# SCH_-_RC2014-_Dev_V1_1_-_freeroute.net
KiCad netlist of a schematic drawn in EasyEDA
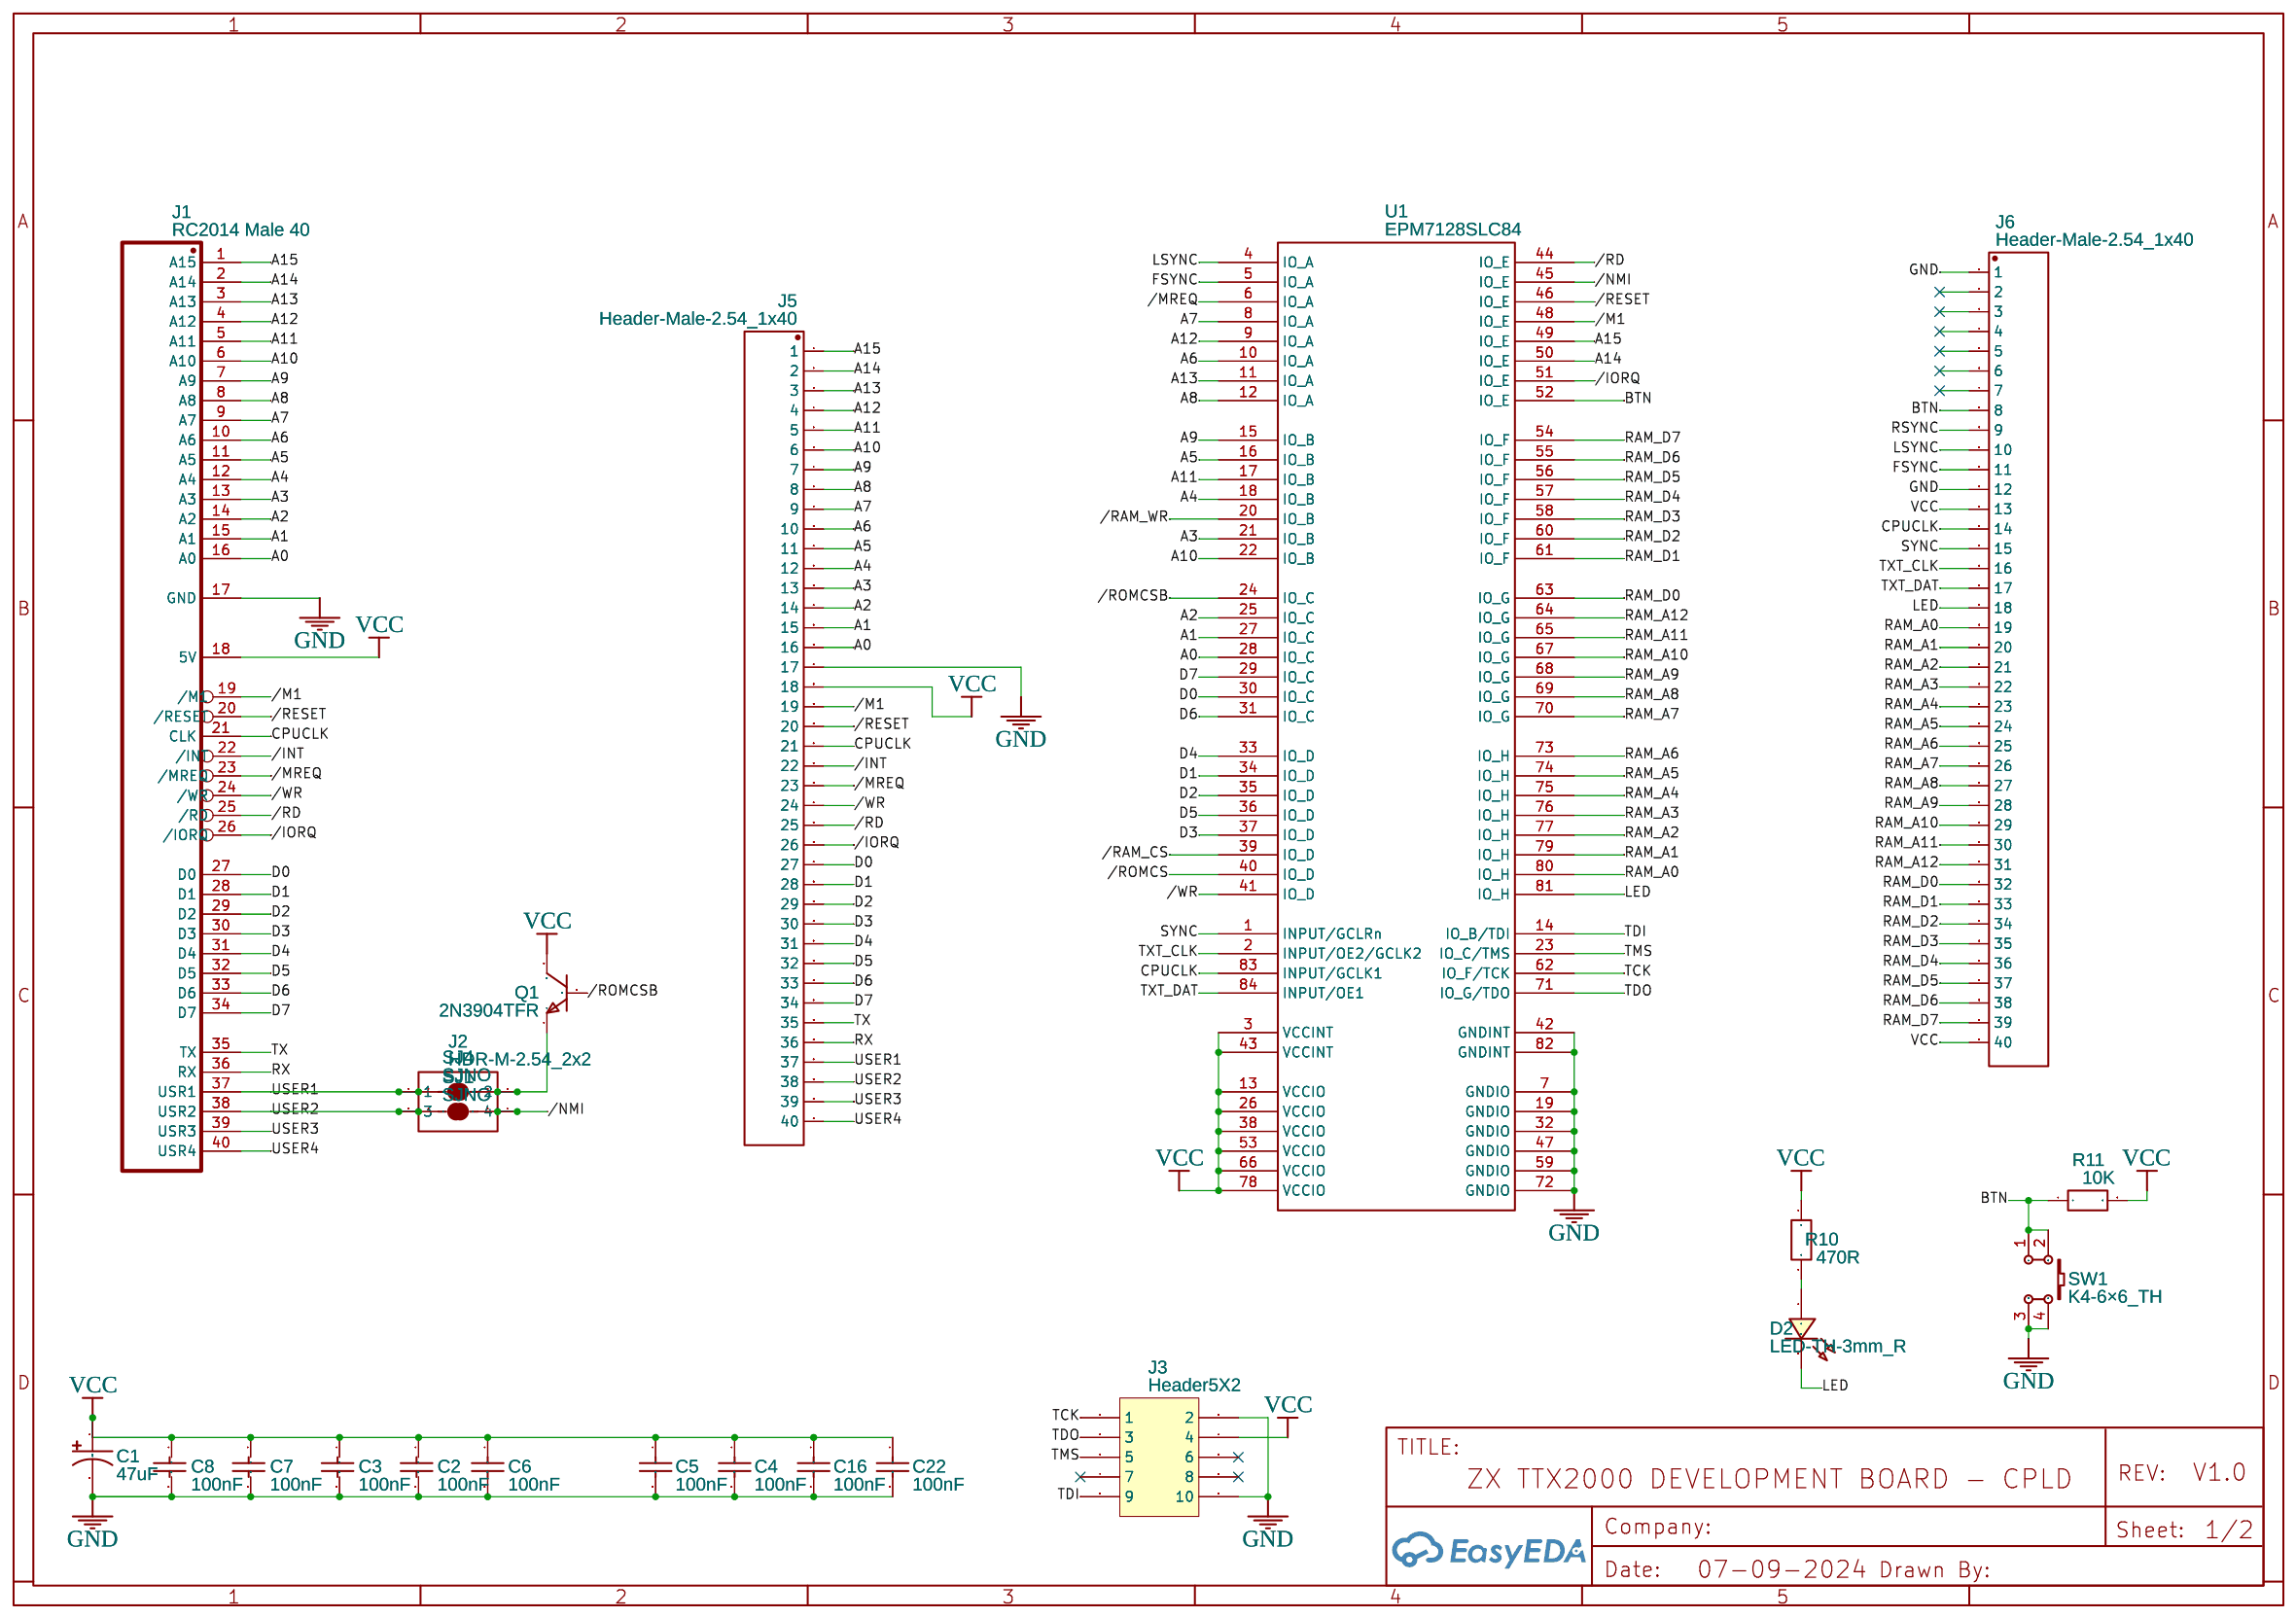
[diagram p0: SCH - RC2014 - Teletext Dev V1.0]
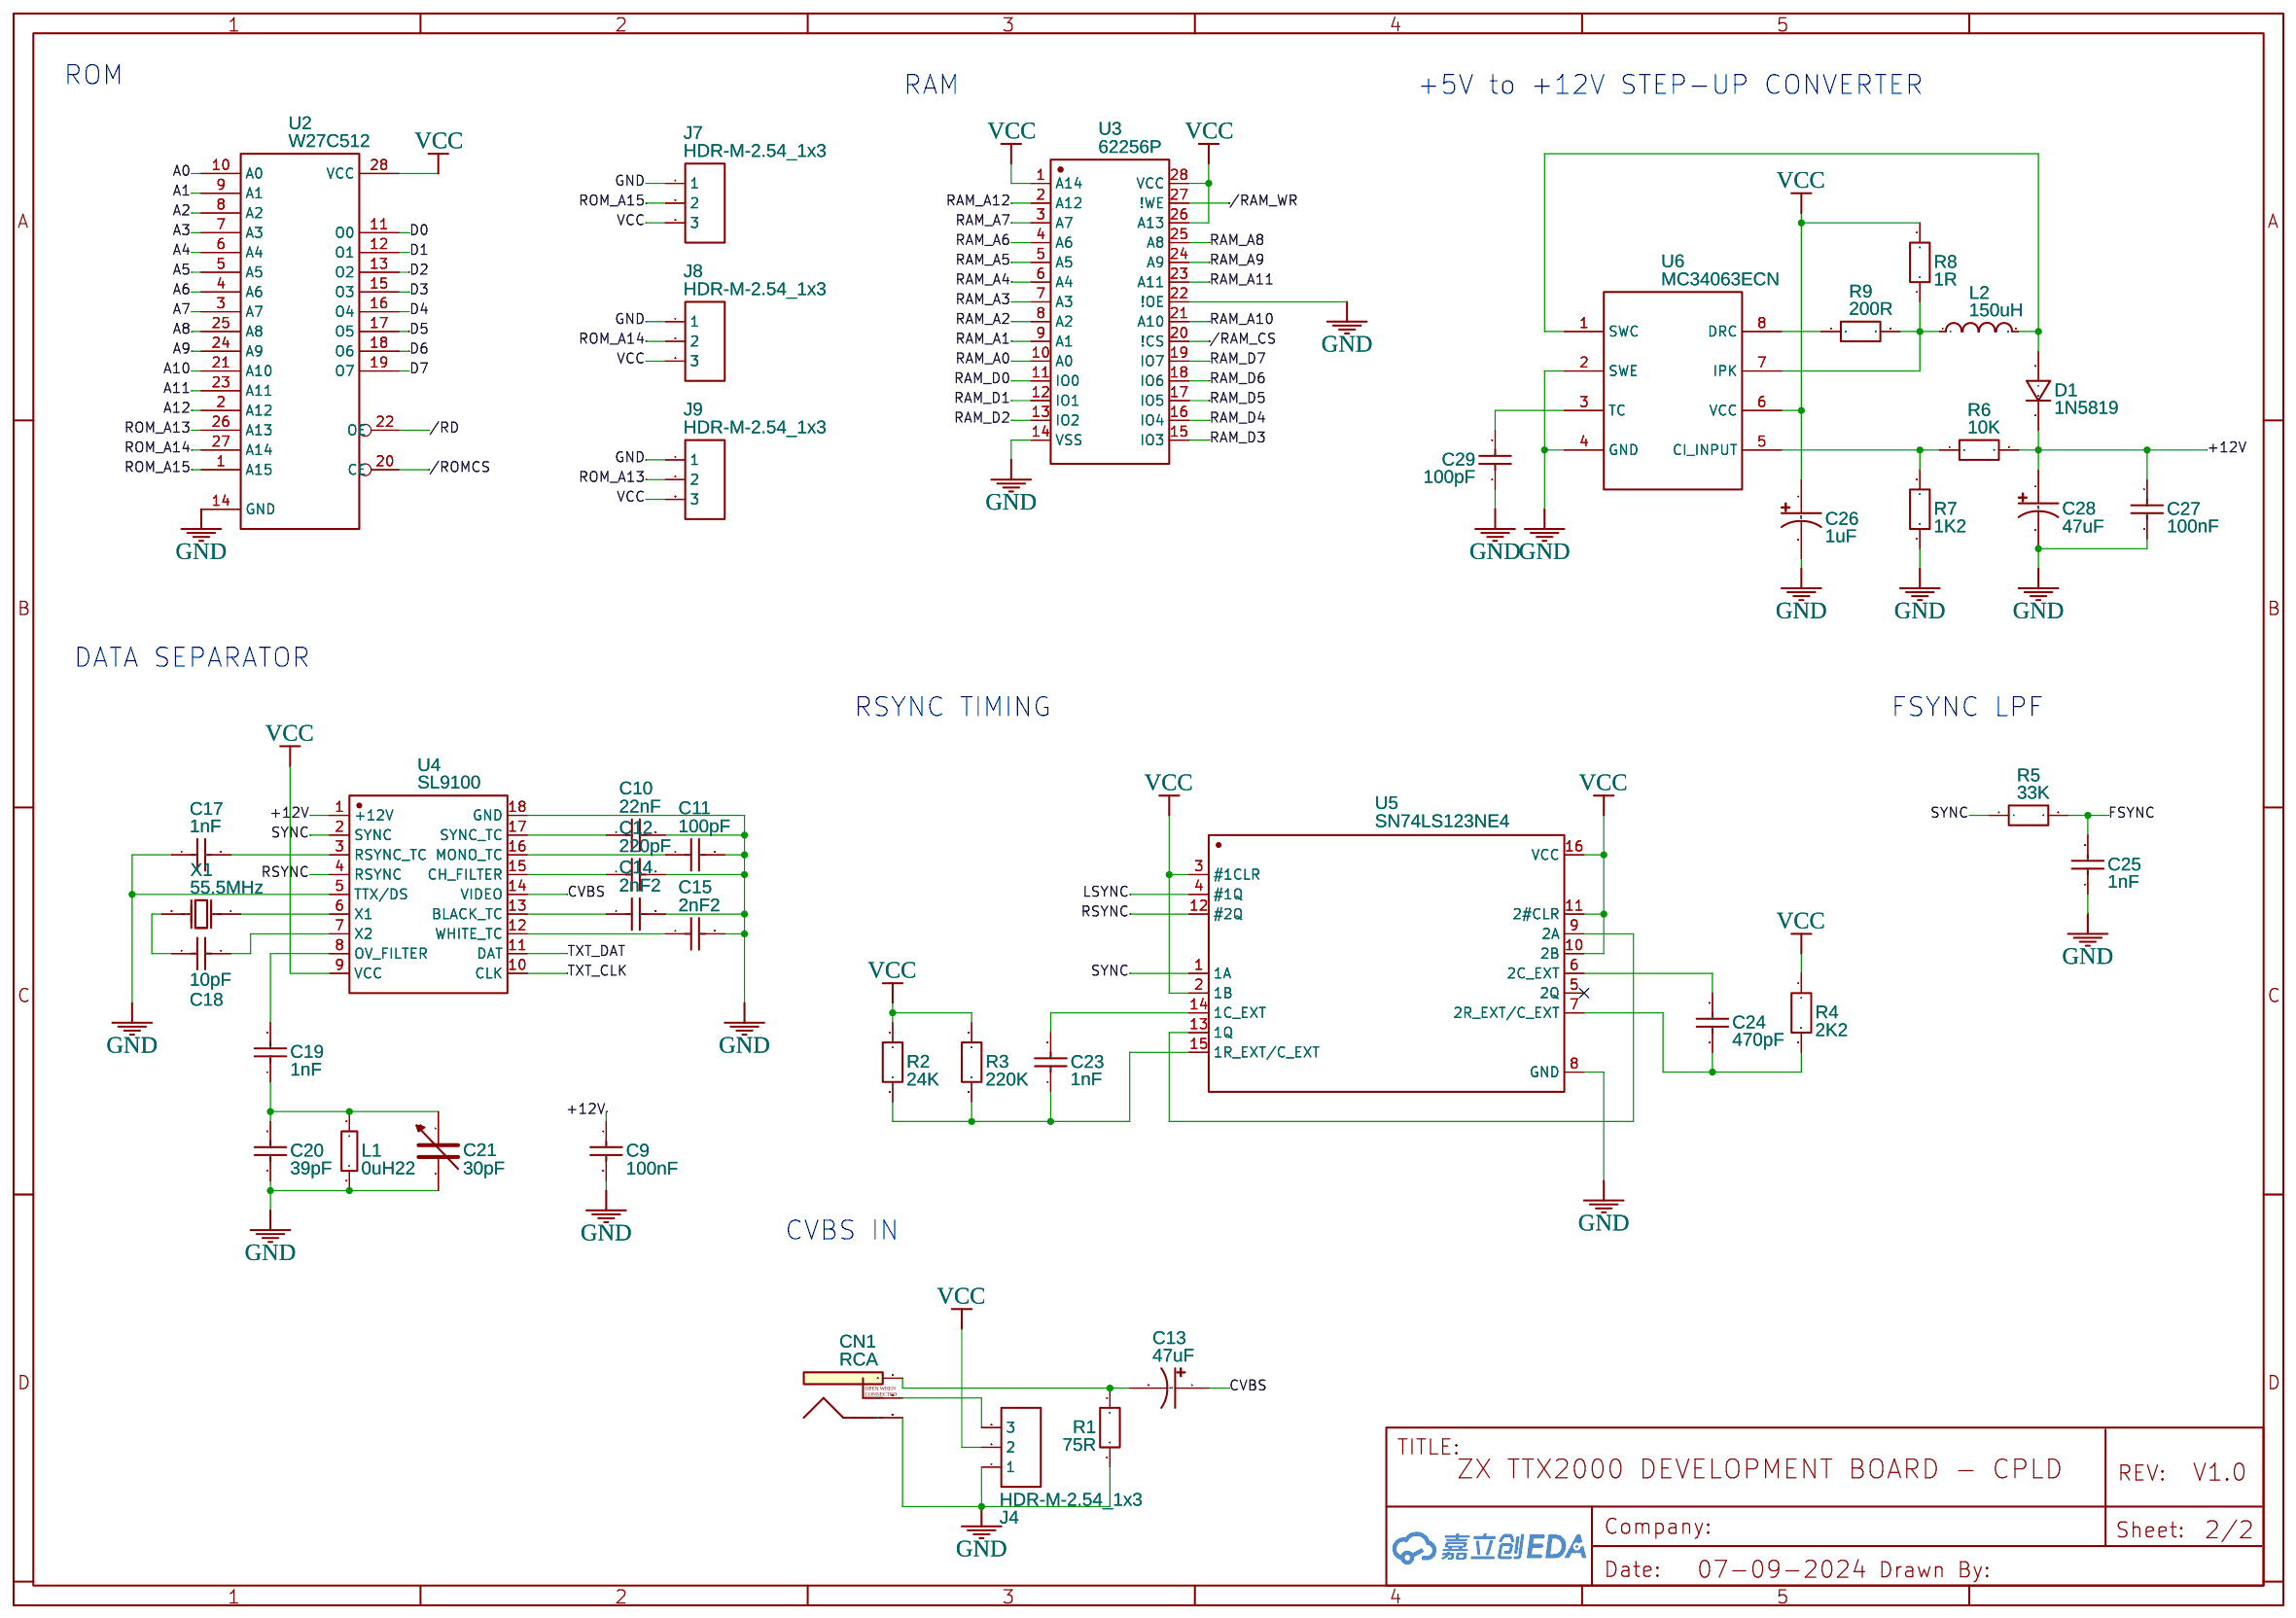
[diagram p1: SCH - ROM & RAM]
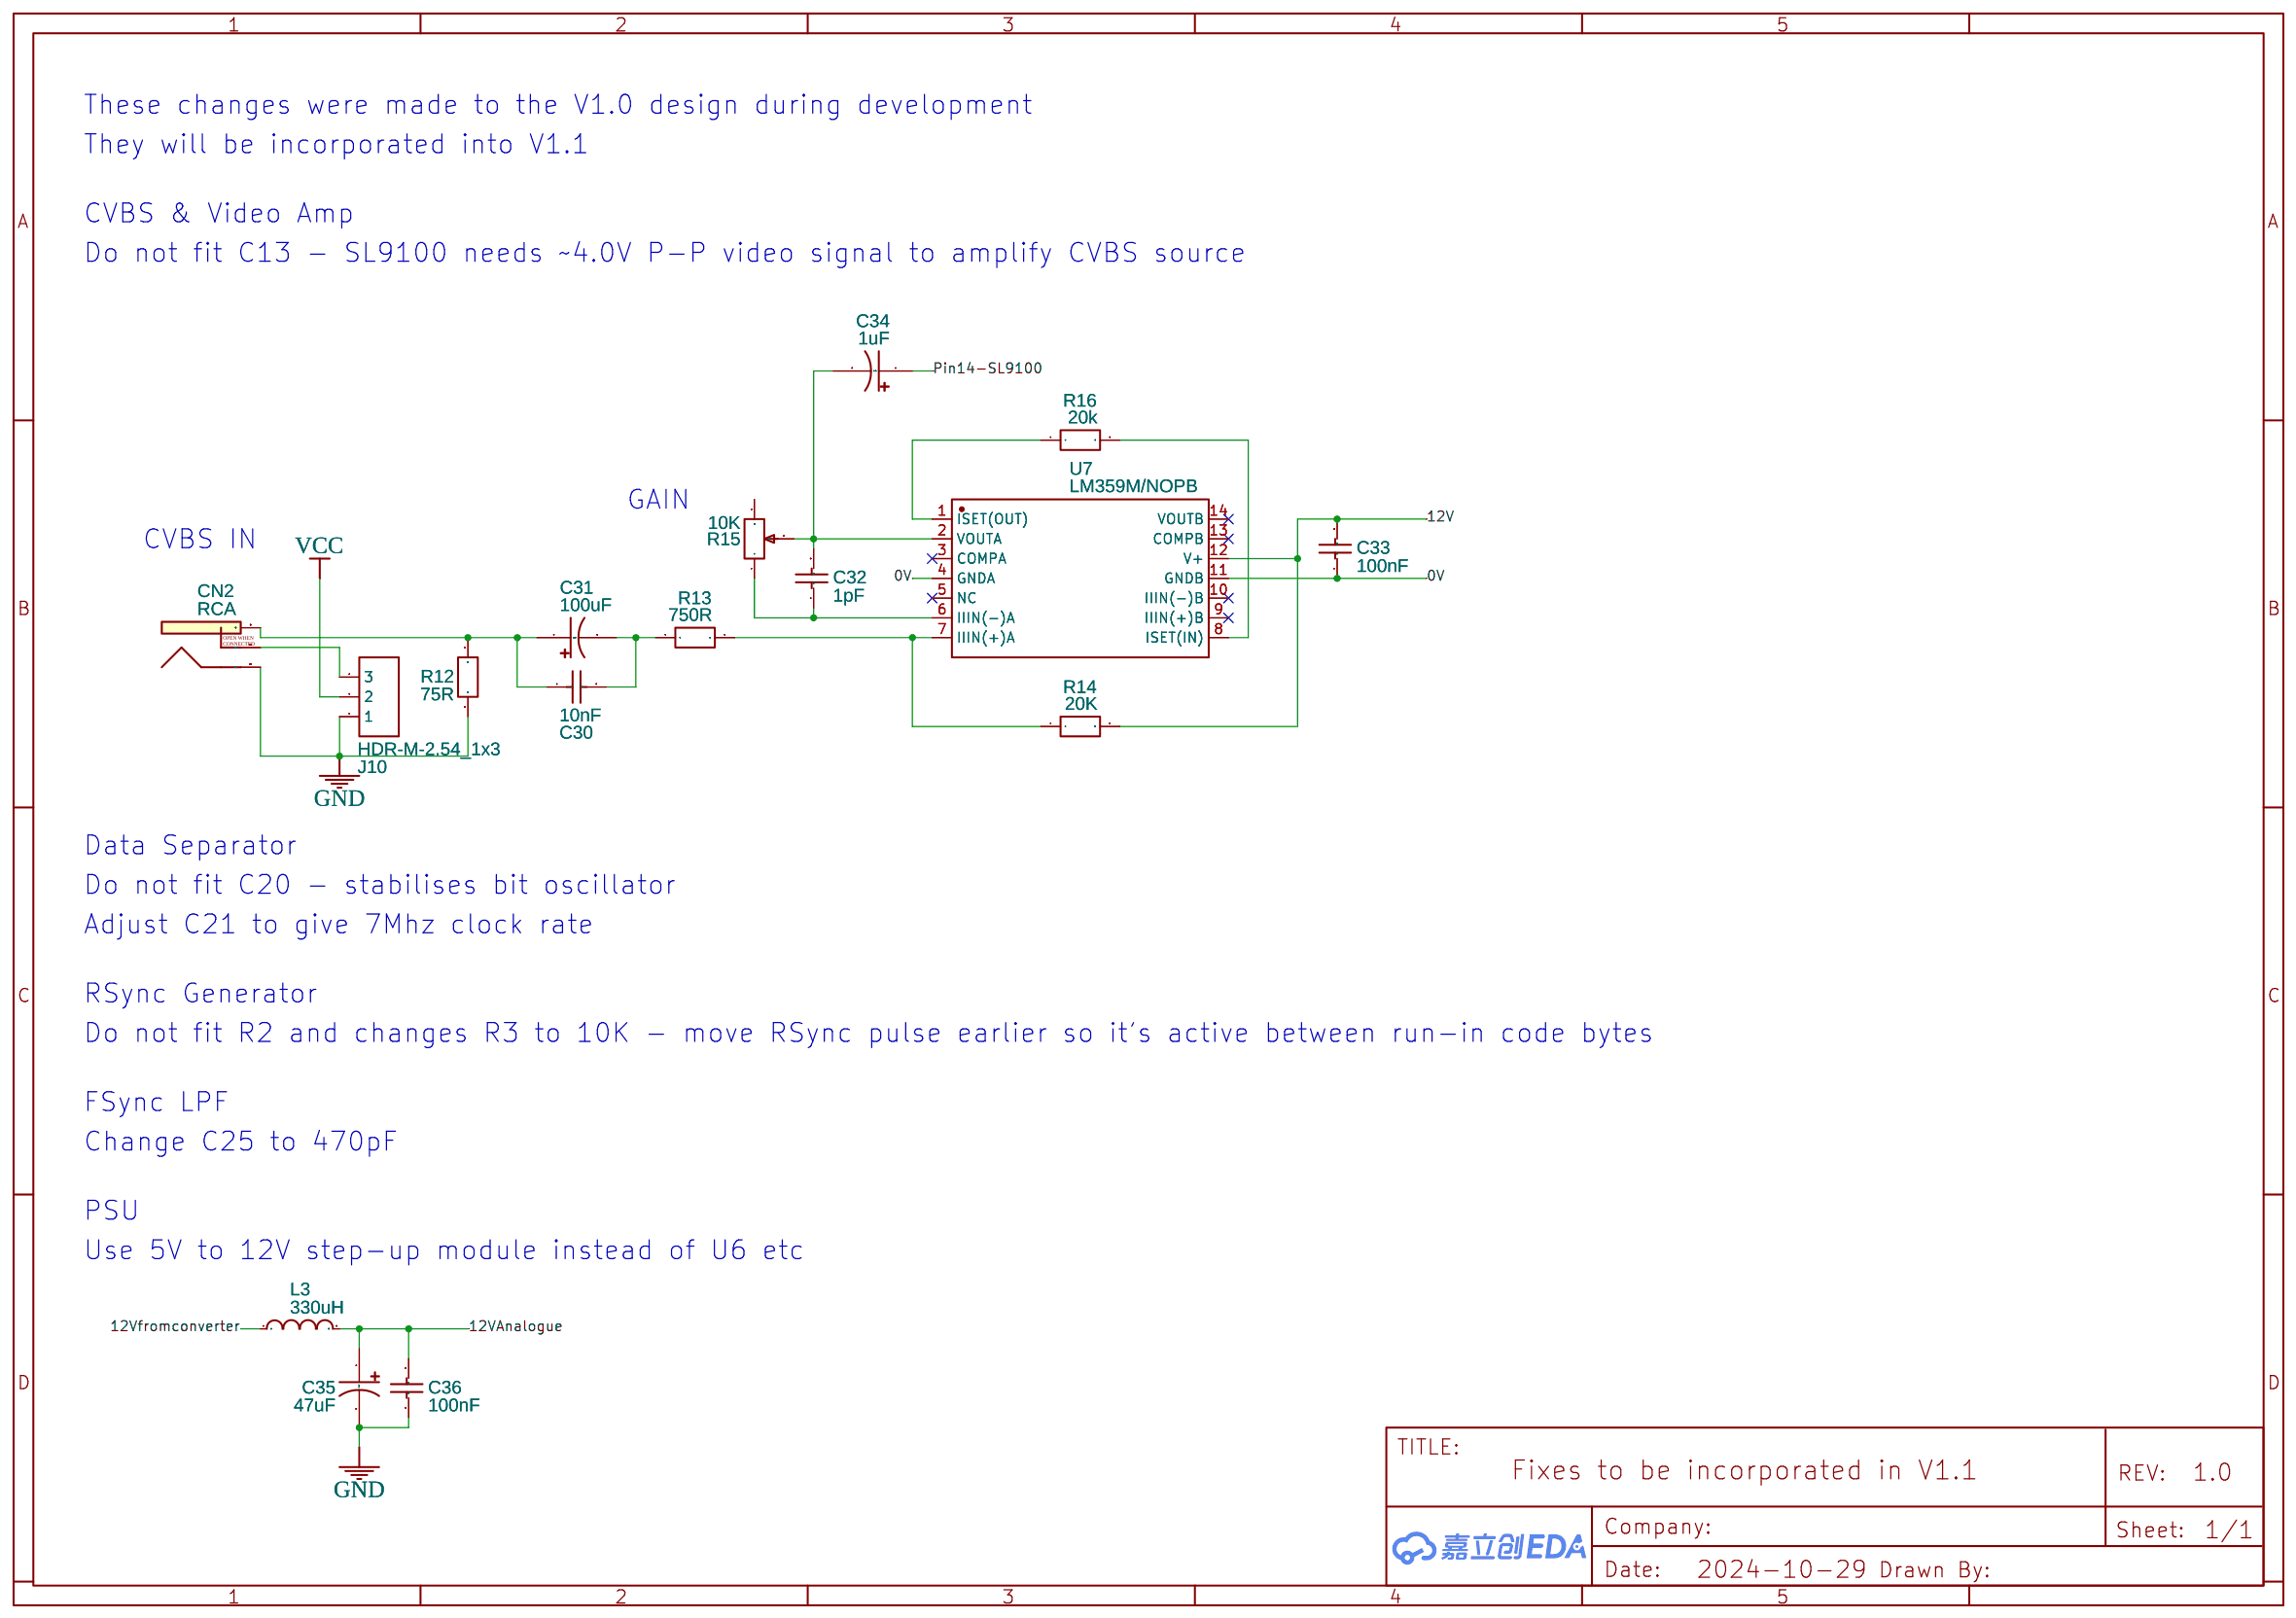
[diagram p2: Fixes]

(export (version "E")
  (design (tool "Eeschema 10.0.6"))
  (components
    (comp (ref "C1")
      (value "47uF")
      (fields
        (field (name "BOM_Manufacturer Part") "KM1H470ME110A00CV0")
        (field (name "BOM_Supplier Part") "C190654")
      )
      (libsource (lib "") (part "KM1H470ME110A00CV0"))
    )
    (comp (ref "C2")
      (value "100nF")
      (fields
        (field (name "BOM_Manufacturer Part") "100nF (104) ±20% 100V")
        (field (name "BOM_Supplier Part") "C72322")
      )
      (libsource (lib "") (part "100nF (104) ±20% 100V_1"))
    )
    (comp (ref "C3")
      (value "100nF")
      (fields
        (field (name "BOM_Manufacturer Part") "100nF (104) ±20% 100V")
        (field (name "BOM_Supplier Part") "C72322")
      )
      (libsource (lib "") (part "100nF (104) ±20% 100V_1"))
    )
    (comp (ref "C4")
      (value "100nF")
      (fields
        (field (name "BOM_Manufacturer Part") "100nF (104) ±20% 100V")
        (field (name "BOM_Supplier Part") "C72322")
      )
      (libsource (lib "") (part "100nF (104) ±20% 100V"))
    )
    (comp (ref "C5")
      (value "100nF")
      (fields
        (field (name "BOM_Manufacturer Part") "100nF (104) ±20% 100V")
        (field (name "BOM_Supplier Part") "C72322")
      )
      (libsource (lib "") (part "100nF (104) ±20% 100V"))
    )
    (comp (ref "C6")
      (value "100nF")
      (fields
        (field (name "BOM_Manufacturer Part") "100nF (104) ±20% 100V")
        (field (name "BOM_Supplier Part") "C72322")
      )
      (libsource (lib "") (part "100nF (104) ±20% 100V"))
    )
    (comp (ref "C7")
      (value "100nF")
      (fields
        (field (name "BOM_Manufacturer Part") "100nF (104) ±20% 100V")
        (field (name "BOM_Supplier Part") "C72322")
      )
      (libsource (lib "") (part "100nF (104) ±20% 100V_1"))
    )
    (comp (ref "C8")
      (value "100nF")
      (fields
        (field (name "BOM_Manufacturer Part") "100nF (104) ±20% 100V")
        (field (name "BOM_Supplier Part") "C72322")
      )
      (libsource (lib "") (part "100nF (104) ±20% 100V_1"))
    )
    (comp (ref "C16")
      (value "100nF")
      (fields
        (field (name "BOM_Manufacturer Part") "100nF (104) ±20% 100V")
        (field (name "BOM_Supplier Part") "C72322")
      )
      (libsource (lib "") (part "100nF (104) ±20% 100V"))
    )
    (comp (ref "C22")
      (value "100nF")
      (fields
        (field (name "BOM_Manufacturer Part") "100nF (104) ±20% 100V")
        (field (name "BOM_Supplier Part") "C72322")
      )
      (libsource (lib "") (part "100nF (104) ±20% 100V"))
    )
    (comp (ref "D2")
      (value "LED-TH-3mm_R")
      (fields
        (field (name "BOM_Manufacturer Part") "204-10SDRD/S530-A3-L")
        (field (name "BOM_Supplier Part") "C84774")
      )
      (libsource (lib "") (part "LED-TH-3mm_R"))
    )
    (comp (ref "J1") (value "RC2014 Male 40") (libsource (lib "") (part "RC2014 Male 40")))
    (comp (ref "J2")
      (value "HDR-M-2.54_2x2")
      (fields (field (name "BOM_Supplier Part") "C66690"))
      (libsource (lib "") (part "HDR-M-2.54_2x2"))
    )
    (comp (ref "J3")
      (value "Header5X2")
      (fields
        (field (name "BOM_Manufacturer Part") "SBH11-PBPC-D05-ST-BK")
        (field (name "BOM_Supplier Part") "S9169-ND")
      )
      (libsource (lib "") (part "Header5X2"))
    )
    (comp (ref "J5")
      (value "Header-Male-2.54_1x40")
      (fields
        (field (name "BOM_Manufacturer Part") "2.54mm 1x40P")
        (field (name "BOM_Supplier Part") "C2337")
      )
      (libsource (lib "") (part "Header-Male-2.54_1x40_1"))
    )
    (comp (ref "J6")
      (value "Header-Male-2.54_1x40")
      (fields
        (field (name "BOM_Manufacturer Part") "2.54mm 1x40P")
        (field (name "BOM_Supplier Part") "C2337")
      )
      (libsource (lib "") (part "Header-Male-2.54_1x40"))
    )
    (comp (ref "Q1")
      (value "2N3904TFR")
      (fields (field (name "BOM_Supplier Part") "C258185"))
      (libsource (lib "") (part "2N3904TFR"))
    )
    (comp (ref "R10") (value "470R") (libsource (lib "") (part "R_AXIAL-0.3_EU_1")))
    (comp (ref "R11") (value "10K") (libsource (lib "") (part "R_AXIAL-0.3_EU")))
    (comp (ref "SJ1") (value "SJNO") (libsource (lib "") (part "SOLDERJUMPERNO")))
    (comp (ref "SJ4") (value "SJNO") (libsource (lib "") (part "SOLDERJUMPERNO")))
    (comp (ref "SW1")
      (value "K4-6×6_TH")
      (fields
        (field (name "BOM_Manufacturer Part") "K2-1102DP-E4SW-04")
        (field (name "BOM_Supplier Part") "C136684")
      )
      (libsource (lib "") (part "K4-6×6_TH"))
    )
    (comp (ref "U1")
      (value "EPM7128SLC84")
      (fields (field (name "BOM_Supplier Part") "692-Z8S18020VEG"))
      (libsource (lib "") (part "EPM7128SLC84"))
    )
    (comp (ref "C9")
      (value "100nF")
      (fields
        (field (name "BOM_Manufacturer Part") "100nF (104) ±20% 100V")
        (field (name "BOM_Supplier Part") "C72322")
      )
      (libsource (lib "") (part "100nF (104) ±20% 100V"))
    )
    (comp (ref "C10")
      (value "22nF")
      (fields
        (field (name "BOM_Manufacturer Part") "100nF (104) ±20% 100V")
        (field (name "BOM_Supplier Part") "C72322")
      )
      (libsource (lib "") (part "100nF (104) ±20% 100V_2"))
    )
    (comp (ref "C11")
      (value "100pF")
      (fields
        (field (name "BOM_Manufacturer Part") "100nF (104) ±20% 100V")
        (field (name "BOM_Supplier Part") "C72322")
      )
      (libsource (lib "") (part "100nF (104) ±20% 100V_2"))
    )
    (comp (ref "C12")
      (value "220pF")
      (fields
        (field (name "BOM_Manufacturer Part") "100nF (104) ±20% 100V")
        (field (name "BOM_Supplier Part") "C72322")
      )
      (libsource (lib "") (part "100nF (104) ±20% 100V_2"))
    )
    (comp (ref "C13")
      (value "47uF")
      (fields
        (field (name "BOM_Manufacturer Part") "KM1H470ME110A00CV0")
        (field (name "BOM_Supplier Part") "C190654")
      )
      (libsource (lib "") (part "KM1H470ME110A00CV0_1"))
    )
    (comp (ref "C14")
      (value "2nF2")
      (fields
        (field (name "BOM_Manufacturer Part") "100nF (104) ±20% 100V")
        (field (name "BOM_Supplier Part") "C72322")
      )
      (libsource (lib "") (part "100nF (104) ±20% 100V_2"))
    )
    (comp (ref "C15")
      (value "2nF2")
      (fields
        (field (name "BOM_Manufacturer Part") "100nF (104) ±20% 100V")
        (field (name "BOM_Supplier Part") "C72322")
      )
      (libsource (lib "") (part "100nF (104) ±20% 100V_2"))
    )
    (comp (ref "C17")
      (value "1nF")
      (fields
        (field (name "BOM_Manufacturer Part") "100nF (104) ±20% 100V")
        (field (name "BOM_Supplier Part") "C72322")
      )
      (libsource (lib "") (part "100nF (104) ±20% 100V_2"))
    )
    (comp (ref "C18")
      (value "10pF")
      (fields
        (field (name "BOM_Manufacturer Part") "100nF (104) ±20% 100V")
        (field (name "BOM_Supplier Part") "C72322")
      )
      (libsource (lib "") (part "100nF (104) ±20% 100V_4"))
    )
    (comp (ref "C19")
      (value "1nF")
      (fields
        (field (name "BOM_Manufacturer Part") "100nF (104) ±20% 100V")
        (field (name "BOM_Supplier Part") "C72322")
      )
      (libsource (lib "") (part "100nF (104) ±20% 100V_1"))
    )
    (comp (ref "C20")
      (value "39pF")
      (fields
        (field (name "BOM_Manufacturer Part") "100nF (104) ±20% 100V")
        (field (name "BOM_Supplier Part") "C72322")
      )
      (libsource (lib "") (part "100nF (104) ±20% 100V_1"))
    )
    (comp (ref "C21") (value "30pF") (libsource (lib "") (part "variable capacitor trimmer")))
    (comp (ref "C23")
      (value "1nF")
      (fields
        (field (name "BOM_Manufacturer Part") "100nF (104) ±20% 100V")
        (field (name "BOM_Supplier Part") "C72322")
      )
      (libsource (lib "") (part "100nF (104) ±20% 100V_1"))
    )
    (comp (ref "C24")
      (value "470pF")
      (fields
        (field (name "BOM_Manufacturer Part") "100nF (104) ±20% 100V")
        (field (name "BOM_Supplier Part") "C72322")
      )
      (libsource (lib "") (part "100nF (104) ±20% 100V_1"))
    )
    (comp (ref "C25")
      (value "1nF")
      (fields
        (field (name "BOM_Manufacturer Part") "100nF (104) ±20% 100V")
        (field (name "BOM_Supplier Part") "C72322")
      )
      (libsource (lib "") (part "100nF (104) ±20% 100V_1"))
    )
    (comp (ref "C26")
      (value "1uF")
      (fields
        (field (name "BOM_Manufacturer Part") "KM1H470ME110A00CV0")
        (field (name "BOM_Supplier Part") "C190654")
      )
      (libsource (lib "") (part "KM1H470ME110A00CV0"))
    )
    (comp (ref "C27")
      (value "100nF")
      (fields
        (field (name "BOM_Manufacturer Part") "100nF (104) ±20% 100V")
        (field (name "BOM_Supplier Part") "C72322")
      )
      (libsource (lib "") (part "100nF (104) ±20% 100V_1"))
    )
    (comp (ref "C28")
      (value "47uF")
      (fields
        (field (name "BOM_Manufacturer Part") "KM1H470ME110A00CV0")
        (field (name "BOM_Supplier Part") "C190654")
      )
      (libsource (lib "") (part "KM1H470ME110A00CV0"))
    )
    (comp (ref "C29")
      (value "100pF")
      (fields
        (field (name "BOM_Manufacturer Part") "100nF (104) ±20% 100V")
        (field (name "BOM_Supplier Part") "C72322")
      )
      (libsource (lib "") (part "100nF (104) ±20% 100V_3"))
    )
    (comp (ref "CN1") (value "RCA") (libsource (lib "") (part "RCA")))
    (comp (ref "D1")
      (value "1N5819")
      (fields (field (name "Manufacturer Part") "1N4001-T") (field (name "Manufacturer") "DIODES(美台)"))
      (libsource (lib "") (part "1N4001-T"))
    )
    (comp (ref "J4")
      (value "HDR-M-2.54_1x3")
      (fields (field (name "BOM_Supplier Part") "C180248"))
      (libsource (lib "") (part "HDR-M-2.54_1x3_1"))
    )
    (comp (ref "J7")
      (value "HDR-M-2.54_1x3")
      (fields (field (name "BOM_Supplier Part") "C180248"))
      (libsource (lib "") (part "HDR-M-2.54_1x3"))
    )
    (comp (ref "J8")
      (value "HDR-M-2.54_1x3")
      (fields (field (name "BOM_Supplier Part") "C180248"))
      (libsource (lib "") (part "HDR-M-2.54_1x3"))
    )
    (comp (ref "J9")
      (value "HDR-M-2.54_1x3")
      (fields (field (name "BOM_Supplier Part") "C180248"))
      (libsource (lib "") (part "HDR-M-2.54_1x3"))
    )
    (comp (ref "L1")
      (value "0uH22")
      (fields (field (name "Manufacturer Part") "AXIAL-0.4"))
      (libsource (lib "") (part "AXIAL-0.4"))
    )
    (comp (ref "L2")
      (value "150uH")
      (fields (field (name "Manufacturer Part") "RCH8011NP-181L") (field (name "Manufacturer") "Sumida(胜美达)"))
      (libsource (lib "") (part "RCH8011NP-181L"))
    )
    (comp (ref "R1") (value "75R") (libsource (lib "") (part "R_AXIAL-0.3_EU")))
    (comp (ref "R2") (value "24K") (libsource (lib "") (part "R_AXIAL-0.3_EU")))
    (comp (ref "R3") (value "220K") (libsource (lib "") (part "R_AXIAL-0.3_EU")))
    (comp (ref "R4") (value "2K2") (libsource (lib "") (part "R_AXIAL-0.3_EU")))
    (comp (ref "R5") (value "33K") (libsource (lib "") (part "R_AXIAL-0.3_EU_1")))
    (comp (ref "R6") (value "10K") (libsource (lib "") (part "R_AXIAL-0.3_EU_1")))
    (comp (ref "R7") (value "1K2") (libsource (lib "") (part "R_AXIAL-0.3_EU_2")))
    (comp (ref "R8") (value "1R") (libsource (lib "") (part "R_AXIAL-0.3_EU_2")))
    (comp (ref "R9") (value "200R") (libsource (lib "") (part "R_AXIAL-0.3_EU_1")))
    (comp (ref "U2") (value "W27C512") (libsource (lib "") (part "W27C512")))
    (comp (ref "U3") (value "62256P") (libsource (lib "") (part "62256P")))
    (comp (ref "U4") (value "SL9100") (libsource (lib "") (part "TMS4464")))
    (comp (ref "U5")
      (value "SN74LS123NE4")
      (fields (field (name "Manufacturer") "TI(德州仪器)"))
      (libsource (lib "") (part "SN74LS123NE4"))
    )
    (comp (ref "U6")
      (value "MC34063ECN")
      (fields (field (name "Manufacturer") "ST(意法半导体)"))
      (libsource (lib "") (part "MC34063ECN"))
    )
    (comp (ref "X1")
      (value "55.5MHz")
      (fields
        (field (name "BOM_Manufacturer Part") "X49UD3MSD2SC")
        (field (name "BOM_Supplier Part") "C11252")
      )
      (libsource (lib "") (part "X49UD3MSD2SC"))
    )
    (comp (ref "C30")
      (value "10nF")
      (fields
        (field (name "BOM_Manufacturer Part") "100nF (104) ±20% 100V")
        (field (name "BOM_Supplier Part") "C72322")
      )
      (libsource (lib "") (part "100nF (104) ±20% 100V_1"))
    )
    (comp (ref "C31")
      (value "100uF")
      (fields
        (field (name "BOM_Manufacturer Part") "KM1H470ME110A00CV0")
        (field (name "BOM_Supplier Part") "C190654")
      )
      (libsource (lib "") (part "KM1H470ME110A00CV0_2"))
    )
    (comp (ref "C32")
      (value "1pF")
      (fields
        (field (name "BOM_Manufacturer Part") "100nF (104) ±20% 100V")
        (field (name "BOM_Supplier Part") "C72322")
      )
      (libsource (lib "") (part "100nF (104) ±20% 100V"))
    )
    (comp (ref "C33")
      (value "100nF")
      (fields
        (field (name "BOM_Manufacturer Part") "100nF (104) ±20% 100V")
        (field (name "BOM_Supplier Part") "C72322")
      )
      (libsource (lib "") (part "100nF (104) ±20% 100V"))
    )
    (comp (ref "C34")
      (value "1uF")
      (fields
        (field (name "BOM_Manufacturer Part") "KM1H470ME110A00CV0")
        (field (name "BOM_Supplier Part") "C190654")
      )
      (libsource (lib "") (part "KM1H470ME110A00CV0_1"))
    )
    (comp (ref "C35")
      (value "47uF")
      (fields
        (field (name "BOM_Manufacturer Part") "KM1H470ME110A00CV0")
        (field (name "BOM_Supplier Part") "C190654")
      )
      (libsource (lib "") (part "KM1H470ME110A00CV0"))
    )
    (comp (ref "C36")
      (value "100nF")
      (fields
        (field (name "BOM_Manufacturer Part") "100nF (104) ±20% 100V")
        (field (name "BOM_Supplier Part") "C72322")
      )
      (libsource (lib "") (part "100nF (104) ±20% 100V"))
    )
    (comp (ref "CN2") (value "RCA") (libsource (lib "") (part "RCA")))
    (comp (ref "J10")
      (value "HDR-M-2.54_1x3")
      (fields (field (name "BOM_Supplier Part") "C180248"))
      (libsource (lib "") (part "HDR-M-2.54_1x3"))
    )
    (comp (ref "L3")
      (value "330uH")
      (fields
        (field (name "Manufacturer Part") "SLF1045T-331M-N")
        (field (name "Manufacturer") "chilisin(奇力新)")
      )
      (libsource (lib "") (part "INDUCTOR_330UH_P5.0"))
    )
    (comp (ref "R12") (value "75R") (libsource (lib "") (part "R_AXIAL-0.3_EU_1")))
    (comp (ref "R13") (value "750R") (libsource (lib "") (part "R_AXIAL-0.3_EU")))
    (comp (ref "R14") (value "20K") (libsource (lib "") (part "R_AXIAL-0.3_EU")))
    (comp (ref "R15")
      (value "10K")
      (fields
        (field (name "BOM_Manufacturer Part") "EVND8AA03B24")
        (field (name "BOM_Supplier Part") "C5017")
      )
      (libsource (lib "") (part "EVND8AA03B24"))
    )
    (comp (ref "R16") (value "20k") (libsource (lib "") (part "R_AXIAL-0.3_EU")))
    (comp (ref "U7")
      (value "LM359M/NOPB")
      (fields (field (name "Manufacturer") "TI(德州仪器)"))
      (libsource (lib "") (part "LM359M/NOPB"))
    )
  )
  (nets
    (net (code "1") (name "+12V") (class "Default")
      (node (ref "C27") (pin "2") (pinfunction "2_2") (pintype "input"))
      (node (ref "C28") (pin "1") (pinfunction "1_1") (pintype "unspecified"))
      (node (ref "C9") (pin "1") (pinfunction "1_1") (pintype "input"))
      (node (ref "D1") (pin "1") (pinfunction "C_1") (pintype "unspecified"))
      (node (ref "R6") (pin "2") (pinfunction "2_2") (pintype "unspecified"))
      (node (ref "U4") (pin "1") (pinfunction "+12V_1") (pintype "unspecified"))
    )
    (net (code "2") (name "0V") (class "Default")
      (node (ref "C33") (pin "1") (pinfunction "1_1") (pintype "input"))
      (node (ref "U7") (pin "11") (pinfunction "GNDB_11") (pintype "unspecified"))
      (node (ref "U7") (pin "4") (pinfunction "GNDA_4") (pintype "unspecified"))
    )
    (net (code "3") (name "12V") (class "Default")
      (node (ref "C33") (pin "2") (pinfunction "2_2") (pintype "input"))
      (node (ref "R14") (pin "2") (pinfunction "2_2") (pintype "unspecified"))
      (node (ref "U7") (pin "12") (pinfunction "V+_12") (pintype "unspecified"))
    )
    (net (code "4") (name "12VAnalogue") (class "Default")
      (node (ref "C35") (pin "1") (pinfunction "1_1") (pintype "unspecified"))
      (node (ref "C36") (pin "2") (pinfunction "2_2") (pintype "input"))
      (node (ref "L3") (pin "2") (pinfunction "2_2") (pintype "unspecified"))
    )
    (net (code "5") (name "12Vfromconverter") (class "Default")
      (node (ref "L3") (pin "1") (pinfunction "1_1") (pintype "unspecified"))
    )
    (net (code "6") (name "A0") (class "Default")
      (node (ref "J1") (pin "16") (pinfunction "A0_16") (pintype "unspecified"))
      (node (ref "J5") (pin "16") (pinfunction "16_16") (pintype "unspecified"))
      (node (ref "U1") (pin "28") (pinfunction "IO_C_28") (pintype "passive"))
      (node (ref "U2") (pin "10") (pinfunction "A0_10") (pintype "input"))
    )
    (net (code "7") (name "A1") (class "Default")
      (node (ref "J1") (pin "15") (pinfunction "A1_15") (pintype "unspecified"))
      (node (ref "J5") (pin "15") (pinfunction "15_15") (pintype "unspecified"))
      (node (ref "U1") (pin "27") (pinfunction "IO_C_27") (pintype "input"))
      (node (ref "U2") (pin "9") (pinfunction "A1_9") (pintype "input"))
    )
    (net (code "8") (name "A2") (class "Default")
      (node (ref "J1") (pin "14") (pinfunction "A2_14") (pintype "unspecified"))
      (node (ref "J5") (pin "14") (pinfunction "14_14") (pintype "unspecified"))
      (node (ref "U1") (pin "25") (pinfunction "IO_C_25") (pintype "bidirectional"))
      (node (ref "U2") (pin "8") (pinfunction "A2_8") (pintype "input"))
    )
    (net (code "9") (name "A3") (class "Default")
      (node (ref "J1") (pin "13") (pinfunction "A3_13") (pintype "unspecified"))
      (node (ref "J5") (pin "13") (pinfunction "13_13") (pintype "unspecified"))
      (node (ref "U1") (pin "21") (pinfunction "IO_B_21") (pintype "bidirectional"))
      (node (ref "U2") (pin "7") (pinfunction "A3_7") (pintype "input"))
    )
    (net (code "10") (name "A4") (class "Default")
      (node (ref "J1") (pin "12") (pinfunction "A4_12") (pintype "unspecified"))
      (node (ref "J5") (pin "12") (pinfunction "12_12") (pintype "unspecified"))
      (node (ref "U1") (pin "18") (pinfunction "IO_B_18") (pintype "bidirectional"))
      (node (ref "U2") (pin "6") (pinfunction "A4_6") (pintype "input"))
    )
    (net (code "11") (name "A5") (class "Default")
      (node (ref "J1") (pin "11") (pinfunction "A5_11") (pintype "unspecified"))
      (node (ref "J5") (pin "11") (pinfunction "11_11") (pintype "unspecified"))
      (node (ref "U1") (pin "16") (pinfunction "IO_B_16") (pintype "bidirectional"))
      (node (ref "U2") (pin "5") (pinfunction "A5_5") (pintype "input"))
    )
    (net (code "12") (name "A6") (class "Default")
      (node (ref "J1") (pin "10") (pinfunction "A6_10") (pintype "unspecified"))
      (node (ref "J5") (pin "10") (pinfunction "10_10") (pintype "unspecified"))
      (node (ref "U1") (pin "10") (pinfunction "IO_A_10") (pintype "bidirectional"))
      (node (ref "U2") (pin "4") (pinfunction "A6_4") (pintype "input"))
    )
    (net (code "13") (name "A7") (class "Default")
      (node (ref "J1") (pin "9") (pinfunction "A7_9") (pintype "unspecified"))
      (node (ref "J5") (pin "9") (pinfunction "9_9") (pintype "unspecified"))
      (node (ref "U1") (pin "8") (pinfunction "IO_A_8") (pintype "bidirectional"))
      (node (ref "U2") (pin "3") (pinfunction "A7_3") (pintype "input"))
    )
    (net (code "14") (name "A8") (class "Default")
      (node (ref "J1") (pin "8") (pinfunction "A8_8") (pintype "unspecified"))
      (node (ref "J5") (pin "8") (pinfunction "8_8") (pintype "unspecified"))
      (node (ref "U1") (pin "12") (pinfunction "IO_A_12") (pintype "bidirectional"))
      (node (ref "U2") (pin "25") (pinfunction "A8_25") (pintype "input"))
    )
    (net (code "15") (name "A9") (class "Default")
      (node (ref "J1") (pin "7") (pinfunction "A9_7") (pintype "unspecified"))
      (node (ref "J5") (pin "7") (pinfunction "7_7") (pintype "unspecified"))
      (node (ref "U1") (pin "15") (pinfunction "IO_B_15") (pintype "bidirectional"))
      (node (ref "U2") (pin "24") (pinfunction "A9_24") (pintype "input"))
    )
    (net (code "16") (name "A10") (class "Default")
      (node (ref "J1") (pin "6") (pinfunction "A10_6") (pintype "unspecified"))
      (node (ref "J5") (pin "6") (pinfunction "6_6") (pintype "unspecified"))
      (node (ref "U1") (pin "22") (pinfunction "IO_B_22") (pintype "output"))
      (node (ref "U2") (pin "21") (pinfunction "A10_21") (pintype "input"))
    )
    (net (code "17") (name "A11") (class "Default")
      (node (ref "J1") (pin "5") (pinfunction "A11_5") (pintype "unspecified"))
      (node (ref "J5") (pin "5") (pinfunction "5_5") (pintype "unspecified"))
      (node (ref "U1") (pin "17") (pinfunction "IO_B_17") (pintype "bidirectional"))
      (node (ref "U2") (pin "23") (pinfunction "A11_23") (pintype "input"))
    )
    (net (code "18") (name "A12") (class "Default")
      (node (ref "J1") (pin "4") (pinfunction "A12_4") (pintype "unspecified"))
      (node (ref "J5") (pin "4") (pinfunction "4_4") (pintype "unspecified"))
      (node (ref "U1") (pin "9") (pinfunction "IO_A_9") (pintype "bidirectional"))
      (node (ref "U2") (pin "2") (pinfunction "A12_2") (pintype "input"))
    )
    (net (code "19") (name "A13") (class "Default")
      (node (ref "J1") (pin "3") (pinfunction "A13_3") (pintype "unspecified"))
      (node (ref "J5") (pin "3") (pinfunction "3_3") (pintype "unspecified"))
      (node (ref "U1") (pin "11") (pinfunction "IO_A_11") (pintype "bidirectional"))
    )
    (net (code "20") (name "A14") (class "Default")
      (node (ref "J1") (pin "2") (pinfunction "A14_2") (pintype "unspecified"))
      (node (ref "J5") (pin "2") (pinfunction "2_2") (pintype "unspecified"))
      (node (ref "U1") (pin "50") (pinfunction "IO_E_50") (pintype "bidirectional"))
    )
    (net (code "21") (name "A15") (class "Default")
      (node (ref "J1") (pin "1") (pinfunction "A15_1") (pintype "unspecified"))
      (node (ref "J5") (pin "1") (pinfunction "1_1") (pintype "unspecified"))
      (node (ref "U1") (pin "49") (pinfunction "IO_E_49") (pintype "bidirectional"))
    )
    (net (code "22") (name "BTN") (class "Default")
      (node (ref "J6") (pin "8") (pinfunction "8_8") (pintype "unspecified"))
      (node (ref "R11") (pin "1") (pinfunction "1_1") (pintype "unspecified"))
      (node (ref "SW1") (pin "1") (pinfunction "1_1") (pintype "unspecified"))
      (node (ref "SW1") (pin "2") (pinfunction "2_2") (pintype "unspecified"))
      (node (ref "U1") (pin "52") (pinfunction "IO_E_52") (pintype "bidirectional"))
    )
    (net (code "23") (name "CPUCLK") (class "Default")
      (node (ref "J1") (pin "21") (pinfunction "CLK_21") (pintype "unspecified"))
      (node (ref "J5") (pin "21") (pinfunction "21_21") (pintype "unspecified"))
      (node (ref "J6") (pin "14") (pinfunction "14_14") (pintype "unspecified"))
      (node (ref "U1") (pin "83") (pinfunction "INPUT/GCLK1_83") (pintype "input"))
    )
    (net (code "24") (name "CVBS") (class "Default")
      (node (ref "C13") (pin "1") (pinfunction "1_1") (pintype "unspecified"))
      (node (ref "U4") (pin "14") (pinfunction "VIDEO_14") (pintype "unspecified"))
    )
    (net (code "25") (name "D0") (class "Default")
      (node (ref "J1") (pin "27") (pinfunction "D0_27") (pintype "unspecified"))
      (node (ref "J5") (pin "27") (pinfunction "27_27") (pintype "unspecified"))
      (node (ref "U1") (pin "30") (pinfunction "IO_C_30") (pintype "bidirectional"))
      (node (ref "U2") (pin "11") (pinfunction "O0_11") (pintype "unspecified"))
    )
    (net (code "26") (name "D1") (class "Default")
      (node (ref "J1") (pin "28") (pinfunction "D1_28") (pintype "unspecified"))
      (node (ref "J5") (pin "28") (pinfunction "28_28") (pintype "unspecified"))
      (node (ref "U1") (pin "34") (pinfunction "IO_D_34") (pintype "input"))
      (node (ref "U2") (pin "12") (pinfunction "O1_12") (pintype "unspecified"))
    )
    (net (code "27") (name "D2") (class "Default")
      (node (ref "J1") (pin "29") (pinfunction "D2_29") (pintype "unspecified"))
      (node (ref "J5") (pin "29") (pinfunction "29_29") (pintype "unspecified"))
      (node (ref "U1") (pin "35") (pinfunction "IO_D_35") (pintype "input"))
      (node (ref "U2") (pin "13") (pinfunction "O2_13") (pintype "unspecified"))
    )
    (net (code "28") (name "D3") (class "Default")
      (node (ref "J1") (pin "30") (pinfunction "D3_30") (pintype "unspecified"))
      (node (ref "J5") (pin "30") (pinfunction "30_30") (pintype "unspecified"))
      (node (ref "U1") (pin "37") (pinfunction "IO_D_37") (pintype "bidirectional"))
      (node (ref "U2") (pin "15") (pinfunction "O3_15") (pintype "unspecified"))
    )
    (net (code "29") (name "D4") (class "Default")
      (node (ref "J1") (pin "31") (pinfunction "D4_31") (pintype "unspecified"))
      (node (ref "J5") (pin "31") (pinfunction "31_31") (pintype "unspecified"))
      (node (ref "U1") (pin "33") (pinfunction "IO_D_33") (pintype "bidirectional"))
      (node (ref "U2") (pin "16") (pinfunction "O4_16") (pintype "unspecified"))
    )
    (net (code "30") (name "D5") (class "Default")
      (node (ref "J1") (pin "32") (pinfunction "D5_32") (pintype "unspecified"))
      (node (ref "J5") (pin "32") (pinfunction "32_32") (pintype "unspecified"))
      (node (ref "U1") (pin "36") (pinfunction "IO_D_36") (pintype "bidirectional"))
      (node (ref "U2") (pin "17") (pinfunction "O5_17") (pintype "unspecified"))
    )
    (net (code "31") (name "D6") (class "Default")
      (node (ref "J1") (pin "33") (pinfunction "D6_33") (pintype "unspecified"))
      (node (ref "J5") (pin "33") (pinfunction "33_33") (pintype "unspecified"))
      (node (ref "U1") (pin "31") (pinfunction "IO_C_31") (pintype "passive"))
      (node (ref "U2") (pin "18") (pinfunction "O6_18") (pintype "unspecified"))
    )
    (net (code "32") (name "D7") (class "Default")
      (node (ref "J1") (pin "34") (pinfunction "D7_34") (pintype "unspecified"))
      (node (ref "J5") (pin "34") (pinfunction "34_34") (pintype "unspecified"))
      (node (ref "U1") (pin "29") (pinfunction "IO_C_29") (pintype "input"))
      (node (ref "U2") (pin "19") (pinfunction "O7_19") (pintype "unspecified"))
    )
    (net (code "33") (name "FSYNC") (class "Default")
      (node (ref "C25") (pin "2") (pinfunction "2_2") (pintype "input"))
      (node (ref "J6") (pin "11") (pinfunction "11_11") (pintype "unspecified"))
      (node (ref "R5") (pin "2") (pinfunction "2_2") (pintype "unspecified"))
      (node (ref "U1") (pin "5") (pinfunction "IO_A_5") (pintype "bidirectional"))
    )
    (net (code "34") (name "GND") (class "Default")
      (node (ref "C1") (pin "2") (pinfunction "2_2") (pintype "unspecified"))
      (node (ref "C10") (pin "2") (pinfunction "2_2") (pintype "input"))
      (node (ref "C11") (pin "2") (pinfunction "2_2") (pintype "input"))
      (node (ref "C12") (pin "2") (pinfunction "2_2") (pintype "input"))
      (node (ref "C14") (pin "2") (pinfunction "2_2") (pintype "input"))
      (node (ref "C15") (pin "2") (pinfunction "2_2") (pintype "input"))
      (node (ref "C16") (pin "2") (pinfunction "2_2") (pintype "input"))
      (node (ref "C17") (pin "1") (pinfunction "1_1") (pintype "input"))
      (node (ref "C2") (pin "2") (pinfunction "2_2") (pintype "input"))
      (node (ref "C20") (pin "1") (pinfunction "1_1") (pintype "input"))
      (node (ref "C21") (pin "2") (pintype "unspecified"))
      (node (ref "C22") (pin "2") (pinfunction "2_2") (pintype "input"))
      (node (ref "C25") (pin "1") (pinfunction "1_1") (pintype "input"))
      (node (ref "C26") (pin "2") (pinfunction "2_2") (pintype "unspecified"))
      (node (ref "C27") (pin "1") (pinfunction "1_1") (pintype "input"))
      (node (ref "C28") (pin "2") (pinfunction "2_2") (pintype "unspecified"))
      (node (ref "C29") (pin "1") (pinfunction "1_1") (pintype "input"))
      (node (ref "C3") (pin "2") (pinfunction "2_2") (pintype "input"))
      (node (ref "C35") (pin "2") (pinfunction "2_2") (pintype "unspecified"))
      (node (ref "C36") (pin "1") (pinfunction "1_1") (pintype "input"))
      (node (ref "C4") (pin "2") (pinfunction "2_2") (pintype "input"))
      (node (ref "C5") (pin "2") (pinfunction "2_2") (pintype "input"))
      (node (ref "C6") (pin "2") (pinfunction "2_2") (pintype "input"))
      (node (ref "C7") (pin "2") (pinfunction "2_2") (pintype "input"))
      (node (ref "C8") (pin "2") (pinfunction "2_2") (pintype "input"))
      (node (ref "C9") (pin "2") (pinfunction "2_2") (pintype "input"))
      (node (ref "CN1") (pin "SHELL") (pinfunction "SHELL_SHELL") (pintype "unspecified"))
      (node (ref "CN2") (pin "SHELL") (pinfunction "SHELL_SHELL") (pintype "unspecified"))
      (node (ref "J1") (pin "17") (pinfunction "GND_17") (pintype "unspecified"))
      (node (ref "J10") (pin "1") (pinfunction "1_1") (pintype "input"))
      (node (ref "J3") (pin "10") (pinfunction "10_10") (pintype "unspecified"))
      (node (ref "J3") (pin "2") (pinfunction "2_2") (pintype "unspecified"))
      (node (ref "J4") (pin "1") (pinfunction "1_1") (pintype "input"))
      (node (ref "J5") (pin "17") (pinfunction "17_17") (pintype "unspecified"))
      (node (ref "J6") (pin "1") (pinfunction "1_1") (pintype "unspecified"))
      (node (ref "J6") (pin "12") (pinfunction "12_12") (pintype "unspecified"))
      (node (ref "J7") (pin "1") (pinfunction "1_1") (pintype "input"))
      (node (ref "J8") (pin "1") (pinfunction "1_1") (pintype "input"))
      (node (ref "J9") (pin "1") (pinfunction "1_1") (pintype "input"))
      (node (ref "L1") (pin "1") (pinfunction "1_1") (pintype "unspecified"))
      (node (ref "R1") (pin "2") (pinfunction "2_2") (pintype "unspecified"))
      (node (ref "R12") (pin "2") (pinfunction "2_2") (pintype "unspecified"))
      (node (ref "R7") (pin "1") (pinfunction "1_1") (pintype "unspecified"))
      (node (ref "SW1") (pin "3") (pinfunction "3_3") (pintype "unspecified"))
      (node (ref "SW1") (pin "4") (pinfunction "4_4") (pintype "unspecified"))
      (node (ref "U1") (pin "19") (pinfunction "GNDIO_19") (pintype "bidirectional"))
      (node (ref "U1") (pin "32") (pinfunction "GNDIO_32") (pintype "bidirectional"))
      (node (ref "U1") (pin "42") (pinfunction "GNDINT_42") (pintype "input"))
      (node (ref "U1") (pin "47") (pinfunction "GNDIO_47") (pintype "bidirectional"))
      (node (ref "U1") (pin "59") (pinfunction "GNDIO_59") (pintype "bidirectional"))
      (node (ref "U1") (pin "7") (pinfunction "GNDIO_7") (pintype "bidirectional"))
      (node (ref "U1") (pin "72") (pinfunction "GNDIO_72") (pintype "bidirectional"))
      (node (ref "U1") (pin "82") (pinfunction "GNDINT_82") (pintype "input"))
      (node (ref "U2") (pin "14") (pinfunction "GND_14") (pintype "passive"))
      (node (ref "U3") (pin "14") (pinfunction "VSS_14") (pintype "unspecified"))
      (node (ref "U3") (pin "22") (pinfunction "!OE_22") (pintype "unspecified"))
      (node (ref "U4") (pin "18") (pinfunction "GND_18") (pintype "unspecified"))
      (node (ref "U4") (pin "5") (pinfunction "TTX/DS_5") (pintype "unspecified"))
      (node (ref "U5") (pin "8") (pinfunction "GND_8") (pintype "unspecified"))
      (node (ref "U6") (pin "2") (pinfunction "SWE_2") (pintype "unspecified"))
      (node (ref "U6") (pin "4") (pinfunction "GND_4") (pintype "unspecified"))
    )
    (net (code "35") (name "LED") (class "Default")
      (node (ref "D2") (pin "2") (pinfunction "2_2") (pintype "unspecified"))
      (node (ref "J6") (pin "18") (pinfunction "18_18") (pintype "unspecified"))
      (node (ref "U1") (pin "81") (pinfunction "IO_H_81") (pintype "bidirectional"))
    )
    (net (code "36") (name "LSYNC") (class "Default")
      (node (ref "J6") (pin "10") (pinfunction "10_10") (pintype "unspecified"))
      (node (ref "U1") (pin "4") (pinfunction "IO_A_4") (pintype "bidirectional"))
      (node (ref "U5") (pin "4") (pinfunction "#1Q_4") (pintype "unspecified"))
    )
    (net (code "37") (name "Net-(C13-Pad2)") (class "Default")
      (node (ref "C13") (pin "2") (pinfunction "2_2") (pintype "unspecified"))
      (node (ref "CN1") (pin "PIN") (pinfunction "PIN_PIN") (pintype "unspecified"))
      (node (ref "R1") (pin "1") (pinfunction "1_1") (pintype "unspecified"))
    )
    (net (code "38") (name "Net-(C19-Pad1)") (class "Default")
      (node (ref "C19") (pin "1") (pinfunction "1_1") (pintype "input"))
      (node (ref "C20") (pin "2") (pinfunction "2_2") (pintype "input"))
      (node (ref "C21") (pin "1") (pintype "unspecified"))
      (node (ref "L1") (pin "2") (pinfunction "2_2") (pintype "unspecified"))
    )
    (net (code "39") (name "Net-(C30-Pad1)") (class "Default")
      (node (ref "C30") (pin "1") (pinfunction "1_1") (pintype "input"))
      (node (ref "C31") (pin "1") (pinfunction "1_1") (pintype "unspecified"))
      (node (ref "CN2") (pin "PIN") (pinfunction "PIN_PIN") (pintype "unspecified"))
      (node (ref "R12") (pin "1") (pinfunction "1_1") (pintype "unspecified"))
    )
    (net (code "40") (name "Net-(C30-Pad2)") (class "Default")
      (node (ref "C30") (pin "2") (pinfunction "2_2") (pintype "input"))
      (node (ref "C31") (pin "2") (pinfunction "2_2") (pintype "unspecified"))
      (node (ref "R13") (pin "1") (pinfunction "1_1") (pintype "unspecified"))
    )
    (net (code "41") (name "Net-(CN1-PadSWITCH)") (class "Default")
      (node (ref "CN1") (pin "SWITCH") (pinfunction "SWITCH_SWITCH") (pintype "unspecified"))
      (node (ref "J4") (pin "3") (pinfunction "3_3") (pintype "input"))
    )
    (net (code "42") (name "Net-(CN2-PadSWITCH)") (class "Default")
      (node (ref "CN2") (pin "SWITCH") (pinfunction "SWITCH_SWITCH") (pintype "unspecified"))
      (node (ref "J10") (pin "3") (pinfunction "3_3") (pintype "input"))
    )
    (net (code "43") (name "Net-(D1-A)") (class "Default")
      (node (ref "D1") (pin "2") (pinfunction "A_2") (pintype "unspecified"))
      (node (ref "L2") (pin "2") (pinfunction "2_2") (pintype "unspecified"))
      (node (ref "U6") (pin "1") (pinfunction "SWC_1") (pintype "unspecified"))
    )
    (net (code "44") (name "Net-(D2-Pad1)") (class "Default")
      (node (ref "D2") (pin "1") (pinfunction "1_1") (pintype "unspecified"))
      (node (ref "R10") (pin "2") (pinfunction "2_2") (pintype "unspecified"))
    )
    (net (code "45") (name "Net-(Q1-E)") (class "Default")
      (node (ref "J2") (pin "2") (pinfunction "2_2") (pintype "input"))
      (node (ref "Q1") (pin "1") (pinfunction "E_1") (pintype "unspecified"))
      (node (ref "SJ4") (pin "2") (pinfunction "2_2") (pintype "unspecified"))
    )
    (net (code "46") (name "Net-(U4-BLACK_TC)") (class "Default")
      (node (ref "C14") (pin "1") (pinfunction "1_1") (pintype "input"))
      (node (ref "U4") (pin "13") (pinfunction "BLACK_TC_13") (pintype "unspecified"))
    )
    (net (code "47") (name "Net-(U4-CH_FILTER)") (class "Default")
      (node (ref "C12") (pin "1") (pinfunction "1_1") (pintype "input"))
      (node (ref "U4") (pin "15") (pinfunction "CH_FILTER_15") (pintype "unspecified"))
    )
    (net (code "48") (name "Net-(U4-MONO_TC)") (class "Default")
      (node (ref "C11") (pin "1") (pinfunction "1_1") (pintype "input"))
      (node (ref "U4") (pin "16") (pinfunction "MONO_TC_16") (pintype "unspecified"))
    )
    (net (code "49") (name "Net-(U4-OV_FILTER)") (class "Default")
      (node (ref "C19") (pin "2") (pinfunction "2_2") (pintype "input"))
      (node (ref "U4") (pin "8") (pinfunction "OV_FILTER_8") (pintype "unspecified"))
    )
    (net (code "50") (name "Net-(U4-RSYNC_TC)") (class "Default")
      (node (ref "C17") (pin "2") (pinfunction "2_2") (pintype "input"))
      (node (ref "U4") (pin "3") (pinfunction "RSYNC_TC_3") (pintype "unspecified"))
    )
    (net (code "51") (name "Net-(U4-SYNC_TC)") (class "Default")
      (node (ref "C10") (pin "1") (pinfunction "1_1") (pintype "input"))
      (node (ref "U4") (pin "17") (pinfunction "SYNC_TC_17") (pintype "unspecified"))
    )
    (net (code "52") (name "Net-(U4-WHITE_TC)") (class "Default")
      (node (ref "C15") (pin "1") (pinfunction "1_1") (pintype "input"))
      (node (ref "U4") (pin "12") (pinfunction "WHITE_TC_12") (pintype "unspecified"))
    )
    (net (code "53") (name "Net-(U4-X1)") (class "Default")
      (node (ref "U4") (pin "6") (pinfunction "X1_6") (pintype "unspecified"))
      (node (ref "X1") (pin "1") (pinfunction "OSC1_1") (pintype "input"))
    )
    (net (code "54") (name "Net-(U4-X2)") (class "Default")
      (node (ref "C18") (pin "2") (pinfunction "2_2") (pintype "input"))
      (node (ref "U4") (pin "7") (pinfunction "X2_7") (pintype "unspecified"))
    )
    (net (code "55") (name "Net-(U5-1C_EXT)") (class "Default")
      (node (ref "C23") (pin "2") (pinfunction "2_2") (pintype "input"))
      (node (ref "U5") (pin "14") (pinfunction "1C_EXT_14") (pintype "unspecified"))
    )
    (net (code "56") (name "Net-(U5-1Q)") (class "Default")
      (node (ref "U5") (pin "13") (pinfunction "1Q_13") (pintype "unspecified"))
      (node (ref "U5") (pin "9") (pinfunction "2A_9") (pintype "unspecified"))
    )
    (net (code "57") (name "Net-(U5-1R_EXT{slash}C_EXT)") (class "Default")
      (node (ref "C23") (pin "1") (pinfunction "1_1") (pintype "input"))
      (node (ref "R2") (pin "2") (pinfunction "2_2") (pintype "unspecified"))
      (node (ref "R3") (pin "2") (pinfunction "2_2") (pintype "unspecified"))
      (node (ref "U5") (pin "15") (pinfunction "1R_EXT/C_EXT_15") (pintype "unspecified"))
    )
    (net (code "58") (name "Net-(U5-2C_EXT)") (class "Default")
      (node (ref "C24") (pin "2") (pinfunction "2_2") (pintype "input"))
      (node (ref "U5") (pin "6") (pinfunction "2C_EXT_6") (pintype "unspecified"))
    )
    (net (code "59") (name "Net-(U5-2R_EXT{slash}C_EXT)") (class "Default")
      (node (ref "C24") (pin "1") (pinfunction "1_1") (pintype "input"))
      (node (ref "R4") (pin "2") (pinfunction "2_2") (pintype "unspecified"))
      (node (ref "U5") (pin "7") (pinfunction "2R_EXT/C_EXT_7") (pintype "unspecified"))
    )
    (net (code "60") (name "Net-(U6-CI_INPUT)") (class "Default")
      (node (ref "R6") (pin "1") (pinfunction "1_1") (pintype "unspecified"))
      (node (ref "R7") (pin "2") (pinfunction "2_2") (pintype "unspecified"))
      (node (ref "U6") (pin "5") (pinfunction "CI_INPUT_5") (pintype "unspecified"))
    )
    (net (code "61") (name "Net-(U6-DRC)") (class "Default")
      (node (ref "R9") (pin "1") (pinfunction "1_1") (pintype "unspecified"))
      (node (ref "U6") (pin "8") (pinfunction "DRC_8") (pintype "unspecified"))
    )
    (net (code "62") (name "Net-(U6-IPK)") (class "Default")
      (node (ref "L2") (pin "1") (pinfunction "1_1") (pintype "unspecified"))
      (node (ref "R8") (pin "1") (pinfunction "1_1") (pintype "unspecified"))
      (node (ref "R9") (pin "2") (pinfunction "2_2") (pintype "unspecified"))
      (node (ref "U6") (pin "7") (pinfunction "IPK_7") (pintype "unspecified"))
    )
    (net (code "63") (name "Net-(U6-TC)") (class "Default")
      (node (ref "C29") (pin "2") (pinfunction "2_2") (pintype "input"))
      (node (ref "U6") (pin "3") (pinfunction "TC_3") (pintype "unspecified"))
    )
    (net (code "64") (name "Net-(U7-IIIN(+)A)") (class "Default")
      (node (ref "R13") (pin "2") (pinfunction "2_2") (pintype "unspecified"))
      (node (ref "R14") (pin "1") (pinfunction "1_1") (pintype "unspecified"))
      (node (ref "U7") (pin "7") (pinfunction "IIIN(+)A_7") (pintype "unspecified"))
    )
    (net (code "65") (name "Net-(U7-IIIN(-)A)") (class "Default")
      (node (ref "C32") (pin "1") (pinfunction "1_1") (pintype "input"))
      (node (ref "R15") (pin "1") (pinfunction "1_1") (pintype "input"))
      (node (ref "U7") (pin "6") (pinfunction "IIIN(-)A_6") (pintype "unspecified"))
    )
    (net (code "66") (name "Net-(U7-ISET(IN))") (class "Default")
      (node (ref "R16") (pin "2") (pinfunction "2_2") (pintype "unspecified"))
      (node (ref "U7") (pin "8") (pinfunction "ISET(IN)_8") (pintype "unspecified"))
    )
    (net (code "67") (name "Net-(U7-ISET(OUT))") (class "Default")
      (node (ref "R16") (pin "1") (pinfunction "1_1") (pintype "unspecified"))
      (node (ref "U7") (pin "1") (pinfunction "ISET(OUT)_1") (pintype "unspecified"))
    )
    (net (code "68") (name "Net-(U7-VOUTA)") (class "Default")
      (node (ref "C32") (pin "2") (pinfunction "2_2") (pintype "input"))
      (node (ref "C34") (pin "2") (pinfunction "2_2") (pintype "unspecified"))
      (node (ref "R15") (pin "2") (pinfunction "2_2") (pintype "input"))
      (node (ref "U7") (pin "2") (pinfunction "VOUTA_2") (pintype "unspecified"))
    )
    (net (code "69") (name "Net-(X1-OSC2)") (class "Default")
      (node (ref "C18") (pin "1") (pinfunction "1_1") (pintype "input"))
      (node (ref "X1") (pin "2") (pinfunction "OSC2_2") (pintype "input"))
    )
    (net (code "70") (name "Pin14-SL9100") (class "Default")
      (node (ref "C34") (pin "1") (pinfunction "1_1") (pintype "unspecified"))
    )
    (net (code "71") (name "RAM_A0") (class "Default")
      (node (ref "J6") (pin "19") (pinfunction "19_19") (pintype "unspecified"))
      (node (ref "U1") (pin "80") (pinfunction "IO_H_80") (pintype "bidirectional"))
      (node (ref "U3") (pin "10") (pinfunction "A0_10") (pintype "unspecified"))
    )
    (net (code "72") (name "RAM_A1") (class "Default")
      (node (ref "J6") (pin "20") (pinfunction "20_20") (pintype "unspecified"))
      (node (ref "U1") (pin "79") (pinfunction "IO_H_79") (pintype "bidirectional"))
      (node (ref "U3") (pin "9") (pinfunction "A1_9") (pintype "unspecified"))
    )
    (net (code "73") (name "RAM_A2") (class "Default")
      (node (ref "J6") (pin "21") (pinfunction "21_21") (pintype "unspecified"))
      (node (ref "U1") (pin "77") (pinfunction "IO_H_77") (pintype "bidirectional"))
      (node (ref "U3") (pin "8") (pinfunction "A2_8") (pintype "unspecified"))
    )
    (net (code "74") (name "RAM_A3") (class "Default")
      (node (ref "J6") (pin "22") (pinfunction "22_22") (pintype "unspecified"))
      (node (ref "U1") (pin "76") (pinfunction "IO_H_76") (pintype "bidirectional"))
      (node (ref "U3") (pin "7") (pinfunction "A3_7") (pintype "unspecified"))
    )
    (net (code "75") (name "RAM_A4") (class "Default")
      (node (ref "J6") (pin "23") (pinfunction "23_23") (pintype "unspecified"))
      (node (ref "U1") (pin "75") (pinfunction "IO_H_75") (pintype "bidirectional"))
      (node (ref "U3") (pin "6") (pinfunction "A4_6") (pintype "unspecified"))
    )
    (net (code "76") (name "RAM_A5") (class "Default")
      (node (ref "J6") (pin "24") (pinfunction "24_24") (pintype "unspecified"))
      (node (ref "U1") (pin "74") (pinfunction "IO_H_74") (pintype "bidirectional"))
      (node (ref "U3") (pin "5") (pinfunction "A5_5") (pintype "unspecified"))
    )
    (net (code "77") (name "RAM_A6") (class "Default")
      (node (ref "J6") (pin "25") (pinfunction "25_25") (pintype "unspecified"))
      (node (ref "U1") (pin "73") (pinfunction "IO_H_73") (pintype "bidirectional"))
      (node (ref "U3") (pin "4") (pinfunction "A6_4") (pintype "unspecified"))
    )
    (net (code "78") (name "RAM_A7") (class "Default")
      (node (ref "J6") (pin "26") (pinfunction "26_26") (pintype "unspecified"))
      (node (ref "U1") (pin "70") (pinfunction "IO_G_70") (pintype "bidirectional"))
      (node (ref "U3") (pin "3") (pinfunction "A7_3") (pintype "unspecified"))
    )
    (net (code "79") (name "RAM_A8") (class "Default")
      (node (ref "J6") (pin "27") (pinfunction "27_27") (pintype "unspecified"))
      (node (ref "U1") (pin "69") (pinfunction "IO_G_69") (pintype "passive"))
      (node (ref "U3") (pin "25") (pinfunction "A8_25") (pintype "unspecified"))
    )
    (net (code "80") (name "RAM_A9") (class "Default")
      (node (ref "J6") (pin "28") (pinfunction "28_28") (pintype "unspecified"))
      (node (ref "U1") (pin "68") (pinfunction "IO_G_68") (pintype "bidirectional"))
      (node (ref "U3") (pin "24") (pinfunction "A9_24") (pintype "unspecified"))
    )
    (net (code "81") (name "RAM_A10") (class "Default")
      (node (ref "J6") (pin "29") (pinfunction "29_29") (pintype "unspecified"))
      (node (ref "U1") (pin "67") (pinfunction "IO_G_67") (pintype "bidirectional"))
      (node (ref "U3") (pin "21") (pinfunction "A10_21") (pintype "unspecified"))
    )
    (net (code "82") (name "RAM_A11") (class "Default")
      (node (ref "J6") (pin "30") (pinfunction "30_30") (pintype "unspecified"))
      (node (ref "U1") (pin "65") (pinfunction "IO_G_65") (pintype "passive"))
      (node (ref "U3") (pin "23") (pinfunction "A11_23") (pintype "unspecified"))
    )
    (net (code "83") (name "RAM_A12") (class "Default")
      (node (ref "J6") (pin "31") (pinfunction "31_31") (pintype "unspecified"))
      (node (ref "U1") (pin "64") (pinfunction "IO_G_64") (pintype "bidirectional"))
      (node (ref "U3") (pin "2") (pinfunction "A12_2") (pintype "unspecified"))
    )
    (net (code "84") (name "RAM_D0") (class "Default")
      (node (ref "J6") (pin "32") (pinfunction "32_32") (pintype "unspecified"))
      (node (ref "U1") (pin "63") (pinfunction "IO_G_63") (pintype "bidirectional"))
      (node (ref "U3") (pin "11") (pinfunction "IO0_11") (pintype "unspecified"))
    )
    (net (code "85") (name "RAM_D1") (class "Default")
      (node (ref "J6") (pin "33") (pinfunction "33_33") (pintype "unspecified"))
      (node (ref "U1") (pin "61") (pinfunction "IO_F_61") (pintype "bidirectional"))
      (node (ref "U3") (pin "12") (pinfunction "IO1_12") (pintype "unspecified"))
    )
    (net (code "86") (name "RAM_D2") (class "Default")
      (node (ref "J6") (pin "34") (pinfunction "34_34") (pintype "unspecified"))
      (node (ref "U1") (pin "60") (pinfunction "IO_F_60") (pintype "bidirectional"))
      (node (ref "U3") (pin "13") (pinfunction "IO2_13") (pintype "unspecified"))
    )
    (net (code "87") (name "RAM_D3") (class "Default")
      (node (ref "J6") (pin "35") (pinfunction "35_35") (pintype "unspecified"))
      (node (ref "U1") (pin "58") (pinfunction "IO_F_58") (pintype "bidirectional"))
      (node (ref "U3") (pin "15") (pinfunction "IO3_15") (pintype "unspecified"))
    )
    (net (code "88") (name "RAM_D4") (class "Default")
      (node (ref "J6") (pin "36") (pinfunction "36_36") (pintype "unspecified"))
      (node (ref "U1") (pin "57") (pinfunction "IO_F_57") (pintype "bidirectional"))
      (node (ref "U3") (pin "16") (pinfunction "IO4_16") (pintype "unspecified"))
    )
    (net (code "89") (name "RAM_D5") (class "Default")
      (node (ref "J6") (pin "37") (pinfunction "37_37") (pintype "unspecified"))
      (node (ref "U1") (pin "56") (pinfunction "IO_F_56") (pintype "bidirectional"))
      (node (ref "U3") (pin "17") (pinfunction "IO5_17") (pintype "unspecified"))
    )
    (net (code "90") (name "RAM_D6") (class "Default")
      (node (ref "J6") (pin "38") (pinfunction "38_38") (pintype "unspecified"))
      (node (ref "U1") (pin "55") (pinfunction "IO_F_55") (pintype "passive"))
      (node (ref "U3") (pin "18") (pinfunction "IO6_18") (pintype "unspecified"))
    )
    (net (code "91") (name "RAM_D7") (class "Default")
      (node (ref "J6") (pin "39") (pinfunction "39_39") (pintype "unspecified"))
      (node (ref "U1") (pin "54") (pinfunction "IO_F_54") (pintype "bidirectional"))
      (node (ref "U3") (pin "19") (pinfunction "IO7_19") (pintype "unspecified"))
    )
    (net (code "92") (name "ROM_A13") (class "Default")
      (node (ref "J9") (pin "2") (pinfunction "2_2") (pintype "input"))
      (node (ref "U2") (pin "26") (pinfunction "A13_26") (pintype "input"))
    )
    (net (code "93") (name "ROM_A14") (class "Default")
      (node (ref "J8") (pin "2") (pinfunction "2_2") (pintype "input"))
      (node (ref "U2") (pin "27") (pinfunction "A14_27") (pintype "input"))
    )
    (net (code "94") (name "ROM_A15") (class "Default")
      (node (ref "J7") (pin "2") (pinfunction "2_2") (pintype "input"))
      (node (ref "U2") (pin "1") (pinfunction "A15_1") (pintype "input"))
    )
    (net (code "95") (name "RSYNC") (class "Default")
      (node (ref "J6") (pin "9") (pinfunction "9_9") (pintype "unspecified"))
      (node (ref "U4") (pin "4") (pinfunction "RSYNC_4") (pintype "unspecified"))
      (node (ref "U5") (pin "12") (pinfunction "#2Q_12") (pintype "unspecified"))
    )
    (net (code "96") (name "RX") (class "Default")
      (node (ref "J1") (pin "36") (pinfunction "RX_36") (pintype "unspecified"))
      (node (ref "J5") (pin "36") (pinfunction "36_36") (pintype "unspecified"))
    )
    (net (code "97") (name "SYNC") (class "Default")
      (node (ref "J6") (pin "15") (pinfunction "15_15") (pintype "unspecified"))
      (node (ref "R5") (pin "1") (pinfunction "1_1") (pintype "unspecified"))
      (node (ref "U1") (pin "1") (pinfunction "INPUT/GCLRn_1") (pintype "input"))
      (node (ref "U4") (pin "2") (pinfunction "SYNC_2") (pintype "unspecified"))
      (node (ref "U5") (pin "1") (pinfunction "1A_1") (pintype "unspecified"))
    )
    (net (code "98") (name "TCK") (class "Default")
      (node (ref "J3") (pin "1") (pinfunction "1_1") (pintype "unspecified"))
      (node (ref "U1") (pin "62") (pinfunction "IO_F/TCK_62") (pintype "bidirectional"))
    )
    (net (code "99") (name "TDI") (class "Default")
      (node (ref "J3") (pin "9") (pinfunction "9_9") (pintype "unspecified"))
      (node (ref "U1") (pin "14") (pinfunction "IO_B/TDI_14") (pintype "bidirectional"))
    )
    (net (code "100") (name "TDO") (class "Default")
      (node (ref "J3") (pin "3") (pinfunction "3_3") (pintype "unspecified"))
      (node (ref "U1") (pin "71") (pinfunction "IO_G/TDO_71") (pintype "bidirectional"))
    )
    (net (code "101") (name "TMS") (class "Default")
      (node (ref "J3") (pin "5") (pinfunction "5_5") (pintype "unspecified"))
      (node (ref "U1") (pin "23") (pinfunction "IO_C/TMS_23") (pintype "bidirectional"))
    )
    (net (code "102") (name "TX") (class "Default")
      (node (ref "J1") (pin "35") (pinfunction "TX_35") (pintype "unspecified"))
      (node (ref "J5") (pin "35") (pinfunction "35_35") (pintype "unspecified"))
    )
    (net (code "103") (name "TXT_CLK") (class "Default")
      (node (ref "J6") (pin "16") (pinfunction "16_16") (pintype "unspecified"))
      (node (ref "U1") (pin "2") (pinfunction "INPUT/OE2/GCLK2_2") (pintype "input"))
      (node (ref "U4") (pin "10") (pinfunction "CLK_10") (pintype "unspecified"))
    )
    (net (code "104") (name "TXT_DAT") (class "Default")
      (node (ref "J6") (pin "17") (pinfunction "17_17") (pintype "unspecified"))
      (node (ref "U1") (pin "84") (pinfunction "INPUT/OE1_84") (pintype "input"))
      (node (ref "U4") (pin "11") (pinfunction "DAT_11") (pintype "unspecified"))
    )
    (net (code "105") (name "USER1") (class "Default")
      (node (ref "J1") (pin "37") (pinfunction "USR1_37") (pintype "unspecified"))
      (node (ref "J2") (pin "1") (pinfunction "1_1") (pintype "input"))
      (node (ref "J5") (pin "37") (pinfunction "37_37") (pintype "unspecified"))
      (node (ref "SJ4") (pin "1") (pinfunction "1_1") (pintype "unspecified"))
    )
    (net (code "106") (name "USER2") (class "Default")
      (node (ref "J1") (pin "38") (pinfunction "USR2_38") (pintype "unspecified"))
      (node (ref "J2") (pin "3") (pinfunction "3_3") (pintype "input"))
      (node (ref "J5") (pin "38") (pinfunction "38_38") (pintype "unspecified"))
      (node (ref "SJ1") (pin "1") (pinfunction "1_1") (pintype "unspecified"))
    )
    (net (code "107") (name "USER3") (class "Default")
      (node (ref "J1") (pin "39") (pinfunction "USR3_39") (pintype "unspecified"))
      (node (ref "J5") (pin "39") (pinfunction "39_39") (pintype "unspecified"))
    )
    (net (code "108") (name "USER4") (class "Default")
      (node (ref "J1") (pin "40") (pinfunction "USR4_40") (pintype "unspecified"))
      (node (ref "J5") (pin "40") (pinfunction "40_40") (pintype "unspecified"))
    )
    (net (code "109") (name "VCC") (class "Default")
      (node (ref "C1") (pin "1") (pinfunction "1_1") (pintype "unspecified"))
      (node (ref "C16") (pin "1") (pinfunction "1_1") (pintype "input"))
      (node (ref "C2") (pin "1") (pinfunction "1_1") (pintype "input"))
      (node (ref "C22") (pin "1") (pinfunction "1_1") (pintype "input"))
      (node (ref "C26") (pin "1") (pinfunction "1_1") (pintype "unspecified"))
      (node (ref "C3") (pin "1") (pinfunction "1_1") (pintype "input"))
      (node (ref "C4") (pin "1") (pinfunction "1_1") (pintype "input"))
      (node (ref "C5") (pin "1") (pinfunction "1_1") (pintype "input"))
      (node (ref "C6") (pin "1") (pinfunction "1_1") (pintype "input"))
      (node (ref "C7") (pin "1") (pinfunction "1_1") (pintype "input"))
      (node (ref "C8") (pin "1") (pinfunction "1_1") (pintype "input"))
      (node (ref "J1") (pin "18") (pinfunction "5V_18") (pintype "unspecified"))
      (node (ref "J10") (pin "2") (pinfunction "2_2") (pintype "input"))
      (node (ref "J3") (pin "4") (pinfunction "4_4") (pintype "unspecified"))
      (node (ref "J4") (pin "2") (pinfunction "2_2") (pintype "input"))
      (node (ref "J5") (pin "18") (pinfunction "18_18") (pintype "unspecified"))
      (node (ref "J6") (pin "13") (pinfunction "13_13") (pintype "unspecified"))
      (node (ref "J6") (pin "40") (pinfunction "40_40") (pintype "unspecified"))
      (node (ref "J7") (pin "3") (pinfunction "3_3") (pintype "input"))
      (node (ref "J8") (pin "3") (pinfunction "3_3") (pintype "input"))
      (node (ref "J9") (pin "3") (pinfunction "3_3") (pintype "input"))
      (node (ref "Q1") (pin "3") (pinfunction "C_3") (pintype "unspecified"))
      (node (ref "R10") (pin "1") (pinfunction "1_1") (pintype "unspecified"))
      (node (ref "R11") (pin "2") (pinfunction "2_2") (pintype "unspecified"))
      (node (ref "R2") (pin "1") (pinfunction "1_1") (pintype "unspecified"))
      (node (ref "R3") (pin "1") (pinfunction "1_1") (pintype "unspecified"))
      (node (ref "R4") (pin "1") (pinfunction "1_1") (pintype "unspecified"))
      (node (ref "R8") (pin "2") (pinfunction "2_2") (pintype "unspecified"))
      (node (ref "U1") (pin "13") (pinfunction "VCCIO_13") (pintype "bidirectional"))
      (node (ref "U1") (pin "26") (pinfunction "VCCIO_26") (pintype "bidirectional"))
      (node (ref "U1") (pin "3") (pinfunction "VCCINT_3") (pintype "bidirectional"))
      (node (ref "U1") (pin "38") (pinfunction "VCCIO_38") (pintype "bidirectional"))
      (node (ref "U1") (pin "43") (pinfunction "VCCINT_43") (pintype "bidirectional"))
      (node (ref "U1") (pin "53") (pinfunction "VCCIO_53") (pintype "bidirectional"))
      (node (ref "U1") (pin "66") (pinfunction "VCCIO_66") (pintype "bidirectional"))
      (node (ref "U1") (pin "78") (pinfunction "VCCIO_78") (pintype "bidirectional"))
      (node (ref "U2") (pin "28") (pinfunction "VCC_28") (pintype "passive"))
      (node (ref "U3") (pin "1") (pinfunction "A14_1") (pintype "unspecified"))
      (node (ref "U3") (pin "26") (pinfunction "A13_26") (pintype "unspecified"))
      (node (ref "U3") (pin "28") (pinfunction "VCC_28") (pintype "unspecified"))
      (node (ref "U4") (pin "9") (pinfunction "VCC_9") (pintype "unspecified"))
      (node (ref "U5") (pin "10") (pinfunction "2B_10") (pintype "unspecified"))
      (node (ref "U5") (pin "11") (pinfunction "2#CLR_11") (pintype "unspecified"))
      (node (ref "U5") (pin "16") (pinfunction "VCC_16") (pintype "unspecified"))
      (node (ref "U5") (pin "2") (pinfunction "1B_2") (pintype "unspecified"))
      (node (ref "U5") (pin "3") (pinfunction "#1CLR_3") (pintype "unspecified"))
      (node (ref "U6") (pin "6") (pinfunction "VCC_6") (pintype "unspecified"))
    )
    (net (code "110") (name "unconnected-(J3-Pad6)") (class "Default")
      (node (ref "J3") (pin "6") (pinfunction "6_6") (pintype "unspecified+no_connect"))
    )
    (net (code "111") (name "unconnected-(J3-Pad7)") (class "Default")
      (node (ref "J3") (pin "7") (pinfunction "7_7") (pintype "unspecified+no_connect"))
    )
    (net (code "112") (name "unconnected-(J3-Pad8)") (class "Default")
      (node (ref "J3") (pin "8") (pinfunction "8_8") (pintype "unspecified+no_connect"))
    )
    (net (code "113") (name "unconnected-(J6-Pad2)") (class "Default")
      (node (ref "J6") (pin "2") (pinfunction "2_2") (pintype "unspecified+no_connect"))
    )
    (net (code "114") (name "unconnected-(J6-Pad3)") (class "Default")
      (node (ref "J6") (pin "3") (pinfunction "3_3") (pintype "unspecified+no_connect"))
    )
    (net (code "115") (name "unconnected-(J6-Pad4)") (class "Default")
      (node (ref "J6") (pin "4") (pinfunction "4_4") (pintype "unspecified+no_connect"))
    )
    (net (code "116") (name "unconnected-(J6-Pad5)") (class "Default")
      (node (ref "J6") (pin "5") (pinfunction "5_5") (pintype "unspecified+no_connect"))
    )
    (net (code "117") (name "unconnected-(J6-Pad6)") (class "Default")
      (node (ref "J6") (pin "6") (pinfunction "6_6") (pintype "unspecified+no_connect"))
    )
    (net (code "118") (name "unconnected-(J6-Pad7)") (class "Default")
      (node (ref "J6") (pin "7") (pinfunction "7_7") (pintype "unspecified+no_connect"))
    )
    (net (code "119") (name "unconnected-(R15-Pad3)") (class "Default")
      (node (ref "R15") (pin "3") (pinfunction "3_3") (pintype "input"))
    )
    (net (code "120") (name "unconnected-(U5-2Q-Pad5)") (class "Default")
      (node (ref "U5") (pin "5") (pinfunction "2Q_5") (pintype "unspecified+no_connect"))
    )
    (net (code "121") (name "unconnected-(U7-COMPA-Pad3)") (class "Default")
      (node (ref "U7") (pin "3") (pinfunction "COMPA_3") (pintype "unspecified+no_connect"))
    )
    (net (code "122") (name "unconnected-(U7-COMPB-Pad13)") (class "Default")
      (node (ref "U7") (pin "13") (pinfunction "COMPB_13") (pintype "unspecified+no_connect"))
    )
    (net (code "123") (name "unconnected-(U7-IIIN(+)B-Pad9)") (class "Default")
      (node (ref "U7") (pin "9") (pinfunction "IIIN(+)B_9") (pintype "unspecified+no_connect"))
    )
    (net (code "124") (name "unconnected-(U7-IIIN(-)B-Pad10)") (class "Default")
      (node (ref "U7") (pin "10") (pinfunction "IIIN(-)B_10") (pintype "unspecified+no_connect"))
    )
    (net (code "125") (name "unconnected-(U7-NC-Pad5)") (class "Default")
      (node (ref "U7") (pin "5") (pinfunction "NC_5") (pintype "unspecified+no_connect"))
    )
    (net (code "126") (name "unconnected-(U7-VOUTB-Pad14)") (class "Default")
      (node (ref "U7") (pin "14") (pinfunction "VOUTB_14") (pintype "unspecified+no_connect"))
    )
    (net (code "127") (name "{slash}INT") (class "Default")
      (node (ref "J1") (pin "22") (pinfunction "/INT_22") (pintype "unspecified"))
      (node (ref "J5") (pin "22") (pinfunction "22_22") (pintype "unspecified"))
    )
    (net (code "128") (name "{slash}IORQ") (class "Default")
      (node (ref "J1") (pin "26") (pinfunction "/IORQ_26") (pintype "unspecified"))
      (node (ref "J5") (pin "26") (pinfunction "26_26") (pintype "unspecified"))
      (node (ref "U1") (pin "51") (pinfunction "IO_E_51") (pintype "passive"))
    )
    (net (code "129") (name "{slash}M1") (class "Default")
      (node (ref "J1") (pin "19") (pinfunction "/M1_19") (pintype "unspecified"))
      (node (ref "J5") (pin "19") (pinfunction "19_19") (pintype "unspecified"))
      (node (ref "U1") (pin "48") (pinfunction "IO_E_48") (pintype "bidirectional"))
    )
    (net (code "130") (name "{slash}MREQ") (class "Default")
      (node (ref "J1") (pin "23") (pinfunction "/MREQ_23") (pintype "unspecified"))
      (node (ref "J5") (pin "23") (pinfunction "23_23") (pintype "unspecified"))
      (node (ref "U1") (pin "6") (pinfunction "IO_A_6") (pintype "bidirectional"))
    )
    (net (code "131") (name "{slash}NMI") (class "Default")
      (node (ref "J2") (pin "4") (pinfunction "4_4") (pintype "input"))
      (node (ref "SJ1") (pin "2") (pinfunction "2_2") (pintype "unspecified"))
      (node (ref "U1") (pin "45") (pinfunction "IO_E_45") (pintype "bidirectional"))
    )
    (net (code "132") (name "{slash}RAM_CS") (class "Default")
      (node (ref "U1") (pin "39") (pinfunction "IO_D_39") (pintype "bidirectional"))
      (node (ref "U3") (pin "20") (pinfunction "!CS_20") (pintype "unspecified"))
    )
    (net (code "133") (name "{slash}RAM_WR") (class "Default")
      (node (ref "U1") (pin "20") (pinfunction "IO_B_20") (pintype "bidirectional"))
      (node (ref "U3") (pin "27") (pinfunction "!WE_27") (pintype "unspecified"))
    )
    (net (code "134") (name "{slash}RD") (class "Default")
      (node (ref "J1") (pin "25") (pinfunction "/RD_25") (pintype "unspecified"))
      (node (ref "J5") (pin "25") (pinfunction "25_25") (pintype "unspecified"))
      (node (ref "U1") (pin "44") (pinfunction "IO_E_44") (pintype "bidirectional"))
      (node (ref "U2") (pin "22") (pinfunction "OE_22") (pintype "input"))
    )
    (net (code "135") (name "{slash}RESET") (class "Default")
      (node (ref "J1") (pin "20") (pinfunction "/RESET_20") (pintype "unspecified"))
      (node (ref "J5") (pin "20") (pinfunction "20_20") (pintype "unspecified"))
      (node (ref "U1") (pin "46") (pinfunction "IO_E_46") (pintype "bidirectional"))
    )
    (net (code "136") (name "{slash}ROMCS") (class "Default")
      (node (ref "U1") (pin "40") (pinfunction "IO_D_40") (pintype "bidirectional"))
      (node (ref "U2") (pin "20") (pinfunction "CE_20") (pintype "input"))
    )
    (net (code "137") (name "{slash}ROMCSB") (class "Default")
      (node (ref "Q1") (pin "2") (pinfunction "B_2") (pintype "unspecified"))
      (node (ref "U1") (pin "24") (pinfunction "IO_C_24") (pintype "bidirectional"))
    )
    (net (code "138") (name "{slash}WR") (class "Default")
      (node (ref "J1") (pin "24") (pinfunction "/WR_24") (pintype "unspecified"))
      (node (ref "J5") (pin "24") (pinfunction "24_24") (pintype "unspecified"))
      (node (ref "U1") (pin "41") (pinfunction "IO_D_41") (pintype "bidirectional"))
    )
  )
)
